# board.net
KiCad netlist of a schematic drawn in EAGLE
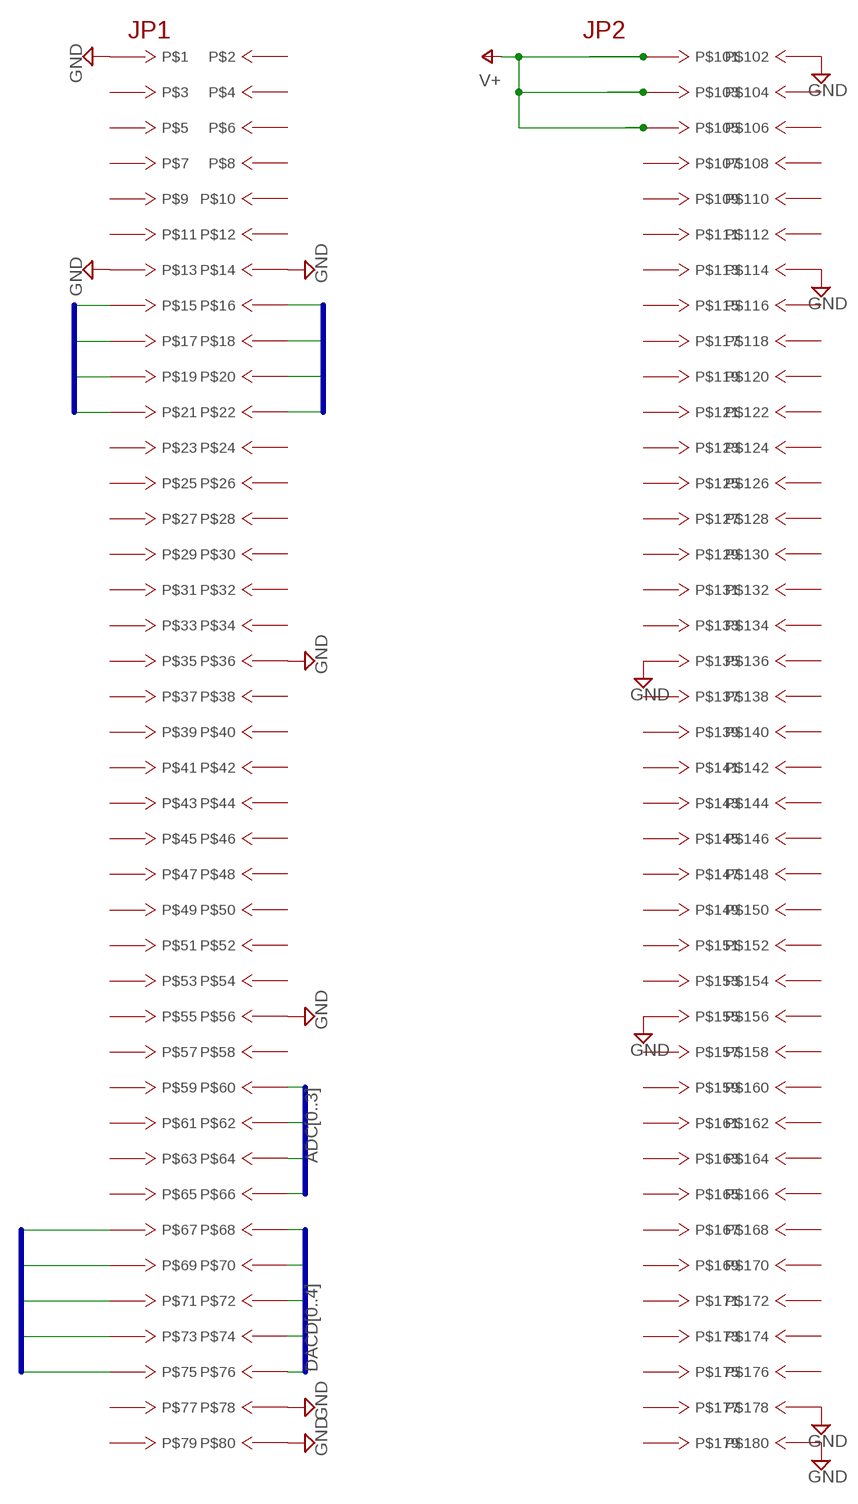
[diagram p0: schematic, sheet 1]
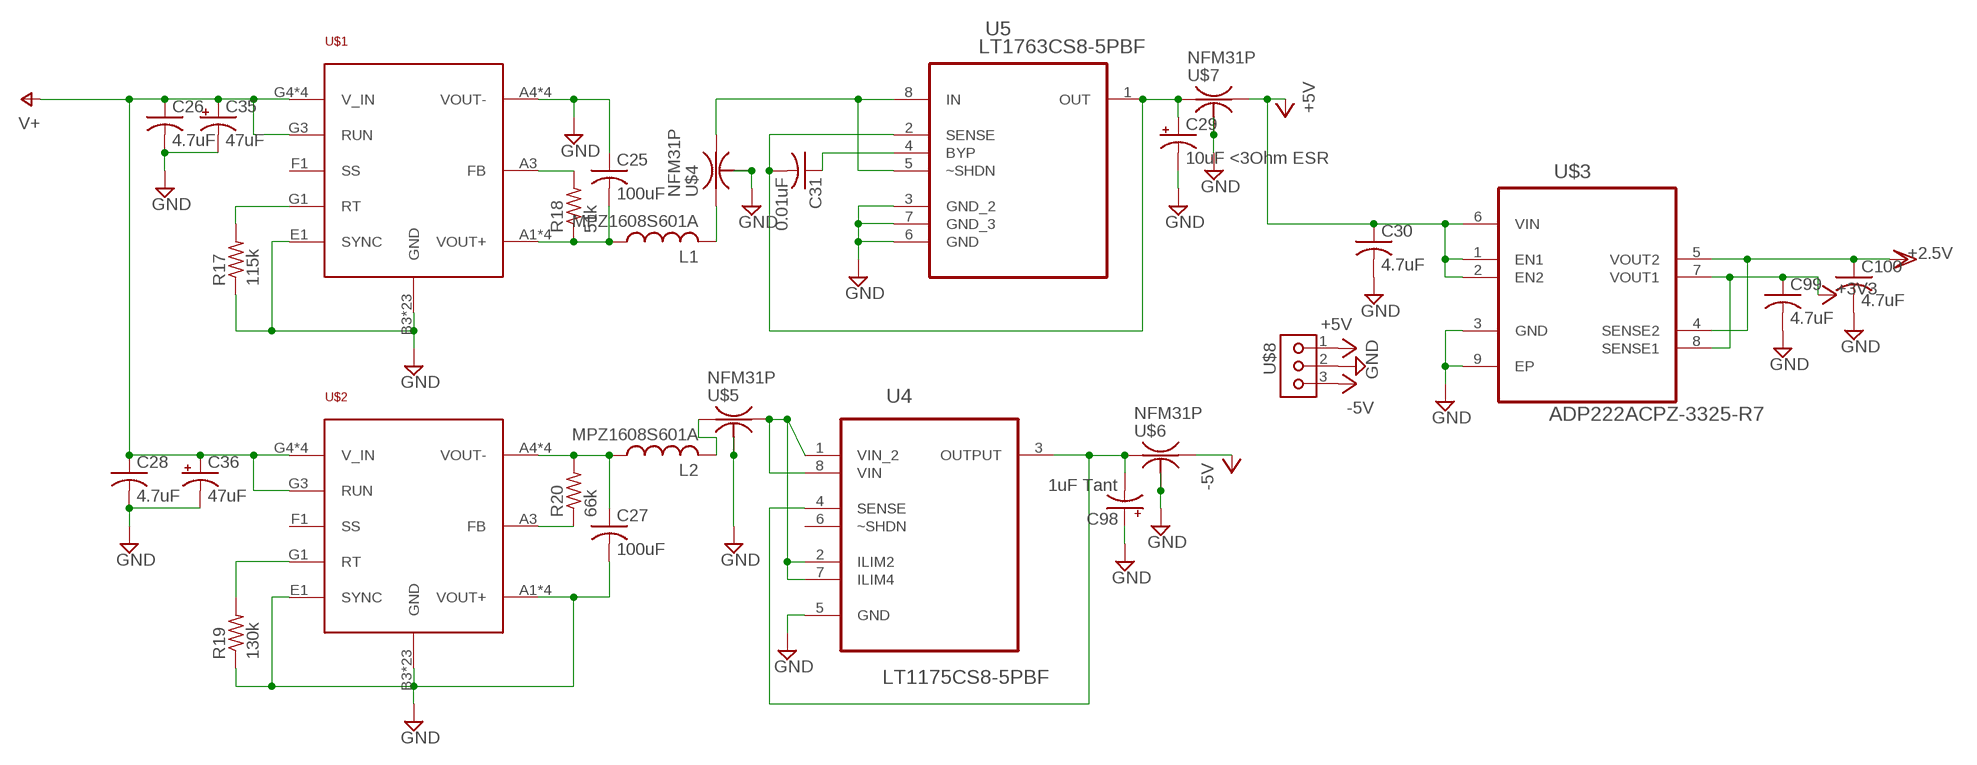
[diagram p1: schematic, sheet 2]
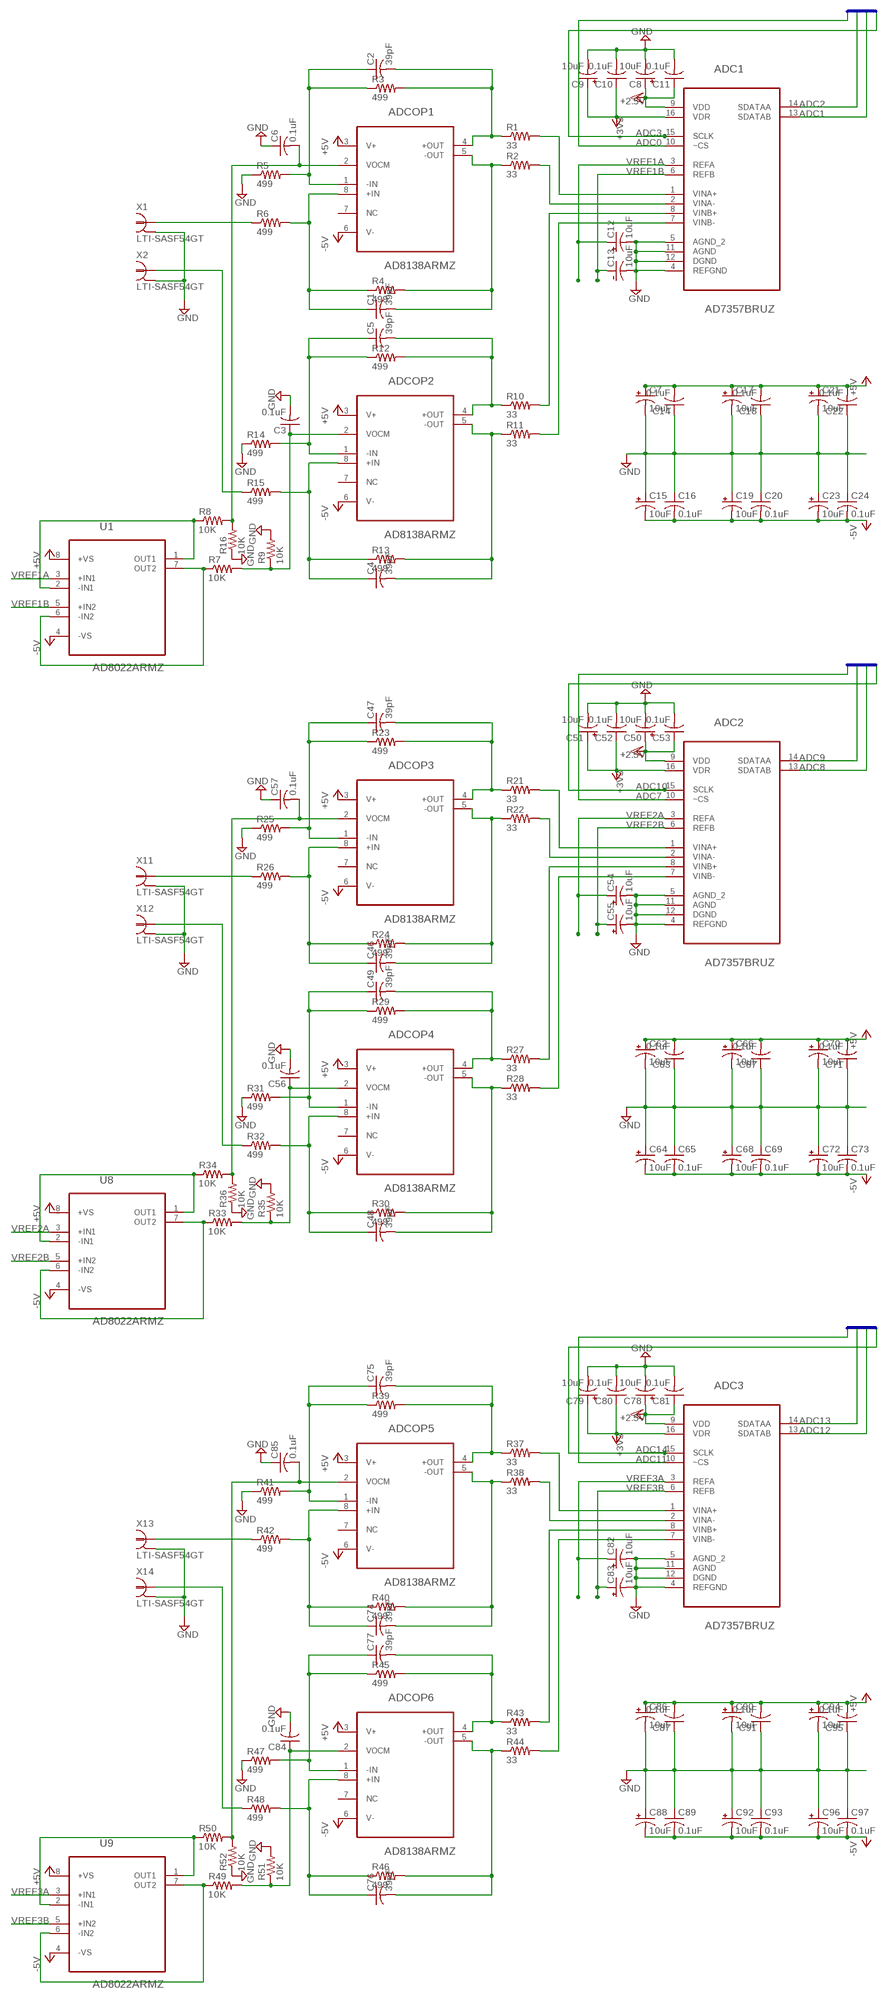
[diagram p2: schematic, sheet 3]
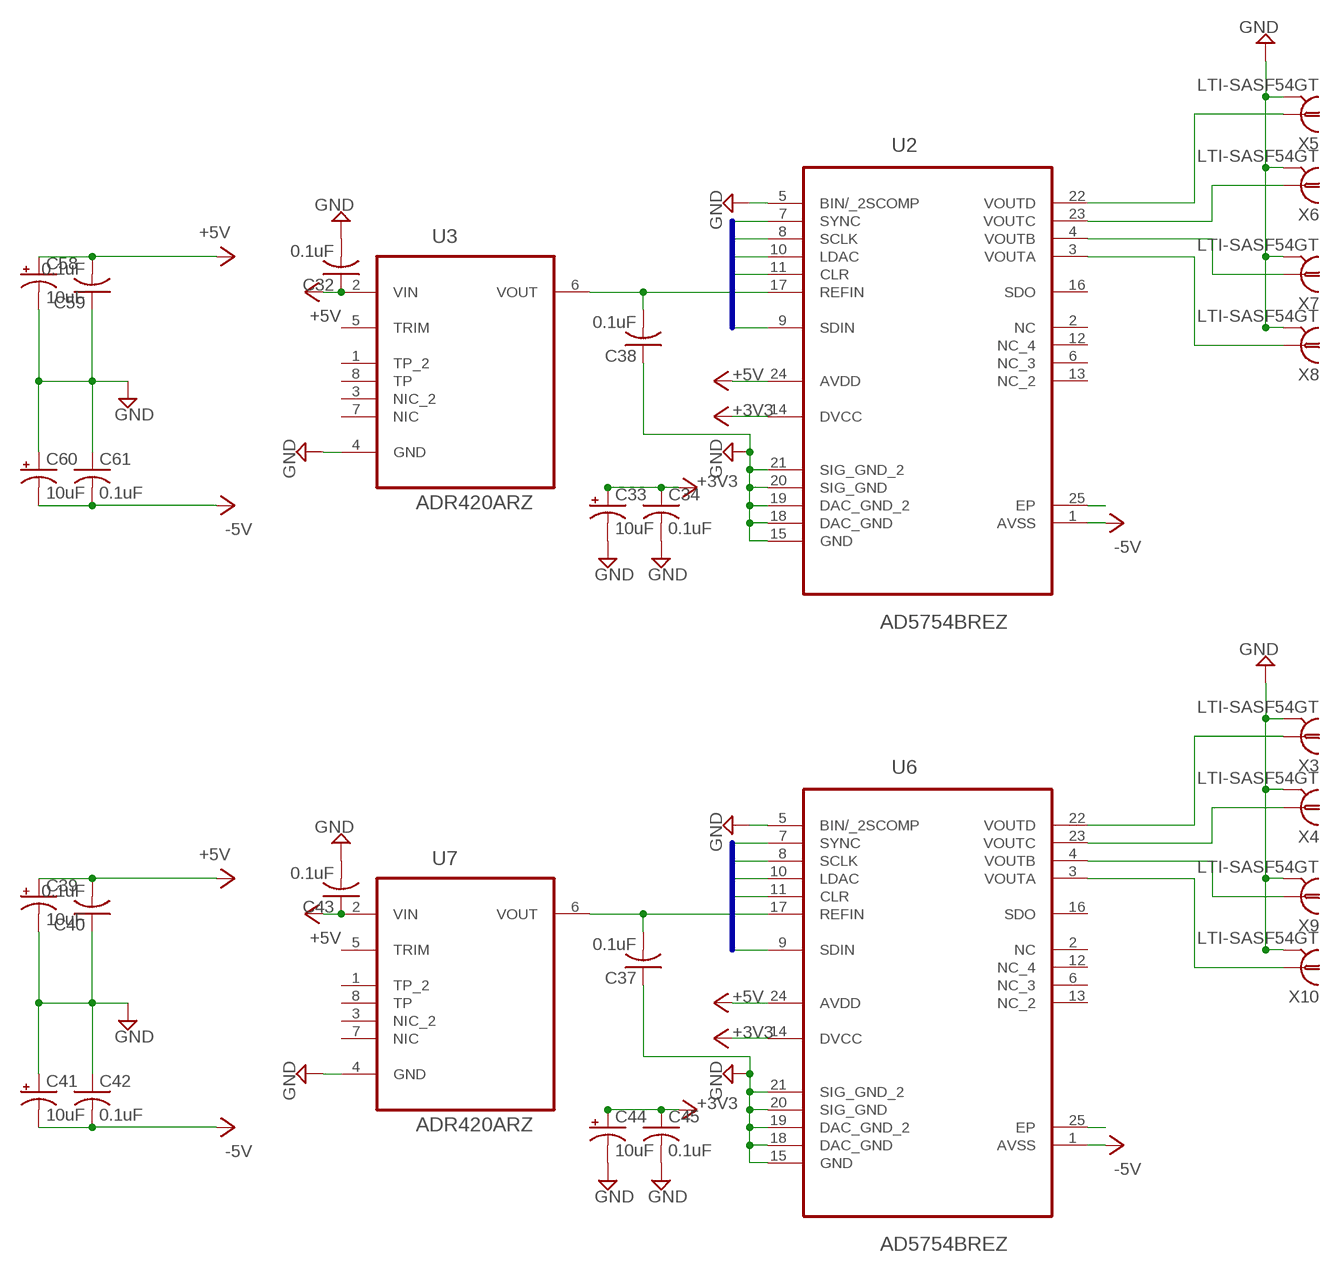
[diagram p3: schematic, sheet 4]

(export (version "E")
  (design (tool "Eeschema 10.0.6"))
  (components
    (comp (ref "J1")
      (value "XEM6310")
      (footprint "eagle-import:XEM6310")
      (libsource (lib "eagle-import") (part "XEM6310"))
    )
    (comp (ref "C32")
      (value "0.1uF")
      (footprint "eagle-import:C0603")
      (libsource (lib "eagle-import") (part "C-USC0603"))
    )
    (comp (ref "C33")
      (value "10uF")
      (footprint "eagle-import:C0603T")
      (libsource (lib "eagle-import") (part "CPOL-US"))
    )
    (comp (ref "C34")
      (value "0.1uF")
      (footprint "eagle-import:C0603")
      (libsource (lib "eagle-import") (part "C-USC0603"))
    )
    (comp (ref "C37")
      (value "0.1uF")
      (footprint "eagle-import:C0603")
      (libsource (lib "eagle-import") (part "C-USC0603"))
    )
    (comp (ref "C38")
      (value "0.1uF")
      (footprint "eagle-import:C0603")
      (libsource (lib "eagle-import") (part "C-USC0603"))
    )
    (comp (ref "C39")
      (value "10uF")
      (footprint "eagle-import:C0603T")
      (libsource (lib "eagle-import") (part "CPOL-US"))
    )
    (comp (ref "C40")
      (value "0.1uF")
      (footprint "eagle-import:C0603")
      (libsource (lib "eagle-import") (part "C-USC0603"))
    )
    (comp (ref "C41")
      (value "10uF")
      (footprint "eagle-import:C0603T")
      (libsource (lib "eagle-import") (part "CPOL-US"))
    )
    (comp (ref "C42")
      (value "0.1uF")
      (footprint "eagle-import:C0603")
      (libsource (lib "eagle-import") (part "C-USC0603"))
    )
    (comp (ref "C43")
      (value "0.1uF")
      (footprint "eagle-import:C0603")
      (libsource (lib "eagle-import") (part "C-USC0603"))
    )
    (comp (ref "C44")
      (value "10uF")
      (footprint "eagle-import:C0603T")
      (libsource (lib "eagle-import") (part "CPOL-US"))
    )
    (comp (ref "C45")
      (value "0.1uF")
      (footprint "eagle-import:C0603")
      (libsource (lib "eagle-import") (part "C-USC0603"))
    )
    (comp (ref "C58")
      (value "10uF")
      (footprint "eagle-import:C0603T")
      (libsource (lib "eagle-import") (part "CPOL-US"))
    )
    (comp (ref "C59")
      (value "0.1uF")
      (footprint "eagle-import:C0603")
      (libsource (lib "eagle-import") (part "C-USC0603"))
    )
    (comp (ref "C60")
      (value "10uF")
      (footprint "eagle-import:C0603T")
      (libsource (lib "eagle-import") (part "CPOL-US"))
    )
    (comp (ref "C61")
      (value "0.1uF")
      (footprint "eagle-import:C0603")
      (libsource (lib "eagle-import") (part "C-USC0603"))
    )
    (comp (ref "U2")
      (value "AD5754BREZ")
      (footprint "eagle-import:SOP65P640X120-25N")
      (libsource (lib "eagle-import") (part "AD5754BREZ"))
    )
    (comp (ref "U3")
      (value "ADR420ARZ")
      (footprint "eagle-import:SOIC127P600X175-8N")
      (libsource (lib "eagle-import") (part "ADR420ARZ"))
    )
    (comp (ref "U6")
      (value "AD5754BREZ")
      (footprint "eagle-import:SOP65P640X120-25N")
      (libsource (lib "eagle-import") (part "AD5754BREZ"))
    )
    (comp (ref "U7")
      (value "ADR420ARZ")
      (footprint "eagle-import:SOIC127P600X175-8N")
      (libsource (lib "eagle-import") (part "ADR420ARZ"))
    )
    (comp (ref "X3")
      (value "LTI-SASF54GT")
      (footprint "eagle-import:LTI-SASF54GT")
      (libsource (lib "eagle-import") (part "LTI-SASF54GT"))
    )
    (comp (ref "X4")
      (value "LTI-SASF54GT")
      (footprint "eagle-import:LTI-SASF54GT")
      (libsource (lib "eagle-import") (part "LTI-SASF54GT"))
    )
    (comp (ref "X5")
      (value "LTI-SASF54GT")
      (footprint "eagle-import:LTI-SASF54GT")
      (libsource (lib "eagle-import") (part "LTI-SASF54GT"))
    )
    (comp (ref "X6")
      (value "LTI-SASF54GT")
      (footprint "eagle-import:LTI-SASF54GT")
      (libsource (lib "eagle-import") (part "LTI-SASF54GT"))
    )
    (comp (ref "X7")
      (value "LTI-SASF54GT")
      (footprint "eagle-import:LTI-SASF54GT")
      (libsource (lib "eagle-import") (part "LTI-SASF54GT"))
    )
    (comp (ref "X8")
      (value "LTI-SASF54GT")
      (footprint "eagle-import:LTI-SASF54GT")
      (libsource (lib "eagle-import") (part "LTI-SASF54GT"))
    )
    (comp (ref "X9")
      (value "LTI-SASF54GT")
      (footprint "eagle-import:LTI-SASF54GT")
      (libsource (lib "eagle-import") (part "LTI-SASF54GT"))
    )
    (comp (ref "X10")
      (value "LTI-SASF54GT")
      (footprint "eagle-import:LTI-SASF54GT")
      (libsource (lib "eagle-import") (part "LTI-SASF54GT"))
    )
    (comp (ref "C25")
      (value "100uF")
      (footprint "eagle-import:C1210")
      (libsource (lib "eagle-import") (part "C-USC1210"))
    )
    (comp (ref "C26")
      (value "4.7uF")
      (footprint "eagle-import:C0603")
      (libsource (lib "eagle-import") (part "C-USC0603"))
    )
    (comp (ref "C27")
      (value "100uF")
      (footprint "eagle-import:C1210")
      (libsource (lib "eagle-import") (part "C-USC1210"))
    )
    (comp (ref "C28")
      (value "4.7uF")
      (footprint "eagle-import:C0603")
      (libsource (lib "eagle-import") (part "C-USC0603"))
    )
    (comp (ref "C29")
      (value "10uF <3Ohm ESR")
      (footprint "eagle-import:C0603T")
      (libsource (lib "eagle-import") (part "CPOL-US"))
    )
    (comp (ref "C30")
      (value "4.7uF")
      (footprint "eagle-import:C0603")
      (libsource (lib "eagle-import") (part "C-USC0603"))
    )
    (comp (ref "C31")
      (value "0.01uF")
      (footprint "eagle-import:C0603")
      (libsource (lib "eagle-import") (part "C-USC0603"))
    )
    (comp (ref "C35")
      (value "47uF")
      (footprint "eagle-import:UD-4X5,8_NICHICON")
      (libsource (lib "eagle-import") (part "CPOL-USUD-4X5,8"))
    )
    (comp (ref "C36")
      (value "47uF")
      (footprint "eagle-import:UD-4X5,8_NICHICON")
      (libsource (lib "eagle-import") (part "CPOL-USUD-4X5,8"))
    )
    (comp (ref "C98")
      (value "1uF Tant")
      (footprint "eagle-import:C0603T")
      (libsource (lib "eagle-import") (part "CPOL-US"))
    )
    (comp (ref "C99")
      (value "4.7uF")
      (footprint "eagle-import:C0603")
      (libsource (lib "eagle-import") (part "C-USC0603"))
    )
    (comp (ref "C100")
      (value "4.7uF")
      (footprint "eagle-import:C0603")
      (libsource (lib "eagle-import") (part "C-USC0603"))
    )
    (comp (ref "L1")
      (value "MPZ1608S601A")
      (footprint "eagle-import:C0603")
      (libsource (lib "eagle-import") (part "L-US"))
    )
    (comp (ref "L2")
      (value "MPZ1608S601A")
      (footprint "eagle-import:C0603")
      (libsource (lib "eagle-import") (part "L-US"))
    )
    (comp (ref "R17")
      (value "115k")
      (footprint "eagle-import:R0603")
      (libsource (lib "eagle-import") (part "R-US_R0603"))
    )
    (comp (ref "R18")
      (value "51k")
      (footprint "eagle-import:R0603")
      (libsource (lib "eagle-import") (part "R-US_R0603"))
    )
    (comp (ref "R19")
      (value "130k")
      (footprint "eagle-import:R0603")
      (libsource (lib "eagle-import") (part "R-US_R0603"))
    )
    (comp (ref "R20")
      (value "66k")
      (footprint "eagle-import:R0603")
      (libsource (lib "eagle-import") (part "R-US_R0603"))
    )
    (comp (ref "U$1")
      (value "LTM8045")
      (footprint "eagle-import:BGA-40")
      (libsource (lib "eagle-import") (part "LTM8045"))
    )
    (comp (ref "U$2")
      (value "LTM8045")
      (footprint "eagle-import:BGA-40")
      (libsource (lib "eagle-import") (part "LTM8045"))
    )
    (comp (ref "U$3")
      (value "ADP222ACPZ-3325-R7")
      (footprint "eagle-import:QFN50P200X200X60-9N")
      (libsource (lib "eagle-import") (part "ADP222ACPZ-3325-R7"))
    )
    (comp (ref "U$4")
      (value "NFM31P")
      (footprint "eagle-import:NFM31P")
      (libsource (lib "eagle-import") (part "NFM31P"))
    )
    (comp (ref "U$5")
      (value "NFM31P")
      (footprint "eagle-import:NFM31P")
      (libsource (lib "eagle-import") (part "NFM31P"))
    )
    (comp (ref "U$6")
      (value "NFM31P")
      (footprint "eagle-import:NFM31P")
      (libsource (lib "eagle-import") (part "NFM31P"))
    )
    (comp (ref "U$7")
      (value "NFM31P")
      (footprint "eagle-import:NFM31P")
      (libsource (lib "eagle-import") (part "NFM31P"))
    )
    (comp (ref "U$8")
      (value "KK3V")
      (footprint "eagle-import:KK-V-3")
      (libsource (lib "eagle-import") (part "KK3V"))
    )
    (comp (ref "U4")
      (value "LT1175CS8-5PBF")
      (footprint "eagle-import:SOIC127P600X175-8N")
      (fields (field (name "MPN") "LT1175CS8-5#PBF"))
      (libsource (lib "eagle-import") (part "LT1175CS8-5PBF"))
    )
    (comp (ref "U5")
      (value "LT1763CS8-5PBF")
      (footprint "eagle-import:SOIC127P600X175-8N")
      (fields (field (name "MPN") "LT1763CS8-5#PBF"))
      (libsource (lib "eagle-import") (part "LT1763CS8-5PBF"))
    )
    (comp (ref "ADC1")
      (value "AD7357BRUZ")
      (footprint "eagle-import:SOP65P640X120-16N")
      (libsource (lib "eagle-import") (part "AD7357BRUZ"))
    )
    (comp (ref "ADC2")
      (value "AD7357BRUZ")
      (footprint "eagle-import:SOP65P640X120-16N")
      (libsource (lib "eagle-import") (part "AD7357BRUZ"))
    )
    (comp (ref "ADC3")
      (value "AD7357BRUZ")
      (footprint "eagle-import:SOP65P640X120-16N")
      (libsource (lib "eagle-import") (part "AD7357BRUZ"))
    )
    (comp (ref "ADCOP1")
      (value "AD8138ARMZ")
      (footprint "eagle-import:SOP65P490X110-8N")
      (libsource (lib "eagle-import") (part "AD8138ARMZ"))
    )
    (comp (ref "ADCOP2")
      (value "AD8138ARMZ")
      (footprint "eagle-import:SOP65P490X110-8N")
      (libsource (lib "eagle-import") (part "AD8138ARMZ"))
    )
    (comp (ref "ADCOP3")
      (value "AD8138ARMZ")
      (footprint "eagle-import:SOP65P490X110-8N")
      (libsource (lib "eagle-import") (part "AD8138ARMZ"))
    )
    (comp (ref "ADCOP4")
      (value "AD8138ARMZ")
      (footprint "eagle-import:SOP65P490X110-8N")
      (libsource (lib "eagle-import") (part "AD8138ARMZ"))
    )
    (comp (ref "ADCOP5")
      (value "AD8138ARMZ")
      (footprint "eagle-import:SOP65P490X110-8N")
      (libsource (lib "eagle-import") (part "AD8138ARMZ"))
    )
    (comp (ref "ADCOP6")
      (value "AD8138ARMZ")
      (footprint "eagle-import:SOP65P490X110-8N")
      (libsource (lib "eagle-import") (part "AD8138ARMZ"))
    )
    (comp (ref "C1")
      (value "39pF")
      (footprint "eagle-import:C0603")
      (libsource (lib "eagle-import") (part "C-USC0603"))
    )
    (comp (ref "C2")
      (value "39pF")
      (footprint "eagle-import:C0603")
      (libsource (lib "eagle-import") (part "C-USC0603"))
    )
    (comp (ref "C3")
      (value "0.1uF")
      (footprint "eagle-import:C0603")
      (libsource (lib "eagle-import") (part "C-USC0603"))
    )
    (comp (ref "C4")
      (value "39pF")
      (footprint "eagle-import:C0603")
      (libsource (lib "eagle-import") (part "C-USC0603"))
    )
    (comp (ref "C5")
      (value "39pF")
      (footprint "eagle-import:C0603")
      (libsource (lib "eagle-import") (part "C-USC0603"))
    )
    (comp (ref "C6")
      (value "0.1uF")
      (footprint "eagle-import:C0603")
      (libsource (lib "eagle-import") (part "C-USC0603"))
    )
    (comp (ref "C7")
      (value "10uF")
      (footprint "eagle-import:C0603T")
      (libsource (lib "eagle-import") (part "CPOL-US"))
    )
    (comp (ref "C8")
      (value "10uF")
      (footprint "eagle-import:C0603T")
      (libsource (lib "eagle-import") (part "CPOL-US"))
    )
    (comp (ref "C9")
      (value "10uF")
      (footprint "eagle-import:C0603T")
      (libsource (lib "eagle-import") (part "CPOL-US"))
    )
    (comp (ref "C10")
      (value "0.1uF")
      (footprint "eagle-import:C0603")
      (libsource (lib "eagle-import") (part "C-USC0603"))
    )
    (comp (ref "C11")
      (value "0.1uF")
      (footprint "eagle-import:C0603")
      (libsource (lib "eagle-import") (part "C-USC0603"))
    )
    (comp (ref "C12")
      (value "10uF")
      (footprint "eagle-import:C0603T")
      (libsource (lib "eagle-import") (part "CPOL-US"))
    )
    (comp (ref "C13")
      (value "10uF")
      (footprint "eagle-import:C0603T")
      (libsource (lib "eagle-import") (part "CPOL-US"))
    )
    (comp (ref "C14")
      (value "0.1uF")
      (footprint "eagle-import:C0603")
      (libsource (lib "eagle-import") (part "C-USC0603"))
    )
    (comp (ref "C15")
      (value "10uF")
      (footprint "eagle-import:C0603T")
      (libsource (lib "eagle-import") (part "CPOL-US"))
    )
    (comp (ref "C16")
      (value "0.1uF")
      (footprint "eagle-import:C0603")
      (libsource (lib "eagle-import") (part "C-USC0603"))
    )
    (comp (ref "C17")
      (value "10uF")
      (footprint "eagle-import:C0603T")
      (libsource (lib "eagle-import") (part "CPOL-US"))
    )
    (comp (ref "C18")
      (value "0.1uF")
      (footprint "eagle-import:C0603")
      (libsource (lib "eagle-import") (part "C-USC0603"))
    )
    (comp (ref "C19")
      (value "10uF")
      (footprint "eagle-import:C0603T")
      (libsource (lib "eagle-import") (part "CPOL-US"))
    )
    (comp (ref "C20")
      (value "0.1uF")
      (footprint "eagle-import:C0603")
      (libsource (lib "eagle-import") (part "C-USC0603"))
    )
    (comp (ref "C21")
      (value "10uF")
      (footprint "eagle-import:C0603T")
      (libsource (lib "eagle-import") (part "CPOL-US"))
    )
    (comp (ref "C22")
      (value "0.1uF")
      (footprint "eagle-import:C0603")
      (libsource (lib "eagle-import") (part "C-USC0603"))
    )
    (comp (ref "C23")
      (value "10uF")
      (footprint "eagle-import:C0603T")
      (libsource (lib "eagle-import") (part "CPOL-US"))
    )
    (comp (ref "C24")
      (value "0.1uF")
      (footprint "eagle-import:C0603")
      (libsource (lib "eagle-import") (part "C-USC0603"))
    )
    (comp (ref "C46")
      (value "39pF")
      (footprint "eagle-import:C0603")
      (libsource (lib "eagle-import") (part "C-USC0603"))
    )
    (comp (ref "C47")
      (value "39pF")
      (footprint "eagle-import:C0603")
      (libsource (lib "eagle-import") (part "C-USC0603"))
    )
    (comp (ref "C48")
      (value "39pF")
      (footprint "eagle-import:C0603")
      (libsource (lib "eagle-import") (part "C-USC0603"))
    )
    (comp (ref "C49")
      (value "39pF")
      (footprint "eagle-import:C0603")
      (libsource (lib "eagle-import") (part "C-USC0603"))
    )
    (comp (ref "C50")
      (value "10uF")
      (footprint "eagle-import:C0603T")
      (libsource (lib "eagle-import") (part "CPOL-US"))
    )
    (comp (ref "C51")
      (value "10uF")
      (footprint "eagle-import:C0603T")
      (libsource (lib "eagle-import") (part "CPOL-US"))
    )
    (comp (ref "C52")
      (value "0.1uF")
      (footprint "eagle-import:C0603")
      (libsource (lib "eagle-import") (part "C-USC0603"))
    )
    (comp (ref "C53")
      (value "0.1uF")
      (footprint "eagle-import:C0603")
      (libsource (lib "eagle-import") (part "C-USC0603"))
    )
    (comp (ref "C54")
      (value "10uF")
      (footprint "eagle-import:C0603T")
      (libsource (lib "eagle-import") (part "CPOL-US"))
    )
    (comp (ref "C55")
      (value "10uF")
      (footprint "eagle-import:C0603T")
      (libsource (lib "eagle-import") (part "CPOL-US"))
    )
    (comp (ref "C56")
      (value "0.1uF")
      (footprint "eagle-import:C0603")
      (libsource (lib "eagle-import") (part "C-USC0603"))
    )
    (comp (ref "C57")
      (value "0.1uF")
      (footprint "eagle-import:C0603")
      (libsource (lib "eagle-import") (part "C-USC0603"))
    )
    (comp (ref "C62")
      (value "10uF")
      (footprint "eagle-import:C0603T")
      (libsource (lib "eagle-import") (part "CPOL-US"))
    )
    (comp (ref "C63")
      (value "0.1uF")
      (footprint "eagle-import:C0603")
      (libsource (lib "eagle-import") (part "C-USC0603"))
    )
    (comp (ref "C64")
      (value "10uF")
      (footprint "eagle-import:C0603T")
      (libsource (lib "eagle-import") (part "CPOL-US"))
    )
    (comp (ref "C65")
      (value "0.1uF")
      (footprint "eagle-import:C0603")
      (libsource (lib "eagle-import") (part "C-USC0603"))
    )
    (comp (ref "C66")
      (value "10uF")
      (footprint "eagle-import:C0603T")
      (libsource (lib "eagle-import") (part "CPOL-US"))
    )
    (comp (ref "C67")
      (value "0.1uF")
      (footprint "eagle-import:C0603")
      (libsource (lib "eagle-import") (part "C-USC0603"))
    )
    (comp (ref "C68")
      (value "10uF")
      (footprint "eagle-import:C0603T")
      (libsource (lib "eagle-import") (part "CPOL-US"))
    )
    (comp (ref "C69")
      (value "0.1uF")
      (footprint "eagle-import:C0603")
      (libsource (lib "eagle-import") (part "C-USC0603"))
    )
    (comp (ref "C70")
      (value "10uF")
      (footprint "eagle-import:C0603T")
      (libsource (lib "eagle-import") (part "CPOL-US"))
    )
    (comp (ref "C71")
      (value "0.1uF")
      (footprint "eagle-import:C0603")
      (libsource (lib "eagle-import") (part "C-USC0603"))
    )
    (comp (ref "C72")
      (value "10uF")
      (footprint "eagle-import:C0603T")
      (libsource (lib "eagle-import") (part "CPOL-US"))
    )
    (comp (ref "C73")
      (value "0.1uF")
      (footprint "eagle-import:C0603")
      (libsource (lib "eagle-import") (part "C-USC0603"))
    )
    (comp (ref "C74")
      (value "39pF")
      (footprint "eagle-import:C0603")
      (libsource (lib "eagle-import") (part "C-USC0603"))
    )
    (comp (ref "C75")
      (value "39pF")
      (footprint "eagle-import:C0603")
      (libsource (lib "eagle-import") (part "C-USC0603"))
    )
    (comp (ref "C76")
      (value "39pF")
      (footprint "eagle-import:C0603")
      (libsource (lib "eagle-import") (part "C-USC0603"))
    )
    (comp (ref "C77")
      (value "39pF")
      (footprint "eagle-import:C0603")
      (libsource (lib "eagle-import") (part "C-USC0603"))
    )
    (comp (ref "C78")
      (value "10uF")
      (footprint "eagle-import:C0603T")
      (libsource (lib "eagle-import") (part "CPOL-US"))
    )
    (comp (ref "C79")
      (value "10uF")
      (footprint "eagle-import:C0603T")
      (libsource (lib "eagle-import") (part "CPOL-US"))
    )
    (comp (ref "C80")
      (value "0.1uF")
      (footprint "eagle-import:C0603")
      (libsource (lib "eagle-import") (part "C-USC0603"))
    )
    (comp (ref "C81")
      (value "0.1uF")
      (footprint "eagle-import:C0603")
      (libsource (lib "eagle-import") (part "C-USC0603"))
    )
    (comp (ref "C82")
      (value "10uF")
      (footprint "eagle-import:C0603T")
      (libsource (lib "eagle-import") (part "CPOL-US"))
    )
    (comp (ref "C83")
      (value "10uF")
      (footprint "eagle-import:C0603T")
      (libsource (lib "eagle-import") (part "CPOL-US"))
    )
    (comp (ref "C84")
      (value "0.1uF")
      (footprint "eagle-import:C0603")
      (libsource (lib "eagle-import") (part "C-USC0603"))
    )
    (comp (ref "C85")
      (value "0.1uF")
      (footprint "eagle-import:C0603")
      (libsource (lib "eagle-import") (part "C-USC0603"))
    )
    (comp (ref "C86")
      (value "10uF")
      (footprint "eagle-import:C0603T")
      (libsource (lib "eagle-import") (part "CPOL-US"))
    )
    (comp (ref "C87")
      (value "0.1uF")
      (footprint "eagle-import:C0603")
      (libsource (lib "eagle-import") (part "C-USC0603"))
    )
    (comp (ref "C88")
      (value "10uF")
      (footprint "eagle-import:C0603T")
      (libsource (lib "eagle-import") (part "CPOL-US"))
    )
    (comp (ref "C89")
      (value "0.1uF")
      (footprint "eagle-import:C0603")
      (libsource (lib "eagle-import") (part "C-USC0603"))
    )
    (comp (ref "C90")
      (value "10uF")
      (footprint "eagle-import:C0603T")
      (libsource (lib "eagle-import") (part "CPOL-US"))
    )
    (comp (ref "C91")
      (value "0.1uF")
      (footprint "eagle-import:C0603")
      (libsource (lib "eagle-import") (part "C-USC0603"))
    )
    (comp (ref "C92")
      (value "10uF")
      (footprint "eagle-import:C0603T")
      (libsource (lib "eagle-import") (part "CPOL-US"))
    )
    (comp (ref "C93")
      (value "0.1uF")
      (footprint "eagle-import:C0603")
      (libsource (lib "eagle-import") (part "C-USC0603"))
    )
    (comp (ref "C94")
      (value "10uF")
      (footprint "eagle-import:C0603T")
      (libsource (lib "eagle-import") (part "CPOL-US"))
    )
    (comp (ref "C95")
      (value "0.1uF")
      (footprint "eagle-import:C0603")
      (libsource (lib "eagle-import") (part "C-USC0603"))
    )
    (comp (ref "C96")
      (value "10uF")
      (footprint "eagle-import:C0603T")
      (libsource (lib "eagle-import") (part "CPOL-US"))
    )
    (comp (ref "C97")
      (value "0.1uF")
      (footprint "eagle-import:C0603")
      (libsource (lib "eagle-import") (part "C-USC0603"))
    )
    (comp (ref "R1")
      (value "33")
      (footprint "eagle-import:R0603")
      (libsource (lib "eagle-import") (part "R-US_R0603"))
    )
    (comp (ref "R2")
      (value "33")
      (footprint "eagle-import:R0603")
      (libsource (lib "eagle-import") (part "R-US_R0603"))
    )
    (comp (ref "R3")
      (value "499")
      (footprint "eagle-import:R0603")
      (libsource (lib "eagle-import") (part "R-US_R0603"))
    )
    (comp (ref "R4")
      (value "499")
      (footprint "eagle-import:R0603")
      (libsource (lib "eagle-import") (part "R-US_R0603"))
    )
    (comp (ref "R5")
      (value "499")
      (footprint "eagle-import:R0603")
      (libsource (lib "eagle-import") (part "R-US_R0603"))
    )
    (comp (ref "R6")
      (value "499")
      (footprint "eagle-import:R0603")
      (libsource (lib "eagle-import") (part "R-US_R0603"))
    )
    (comp (ref "R7")
      (value "10K")
      (footprint "eagle-import:R0603")
      (libsource (lib "eagle-import") (part "R-US_R0603"))
    )
    (comp (ref "R8")
      (value "10K")
      (footprint "eagle-import:R0603")
      (libsource (lib "eagle-import") (part "R-US_R0603"))
    )
    (comp (ref "R9")
      (value "10K")
      (footprint "eagle-import:R0603")
      (libsource (lib "eagle-import") (part "R-US_R0603"))
    )
    (comp (ref "R10")
      (value "33")
      (footprint "eagle-import:R0603")
      (libsource (lib "eagle-import") (part "R-US_R0603"))
    )
    (comp (ref "R11")
      (value "33")
      (footprint "eagle-import:R0603")
      (libsource (lib "eagle-import") (part "R-US_R0603"))
    )
    (comp (ref "R12")
      (value "499")
      (footprint "eagle-import:R0603")
      (libsource (lib "eagle-import") (part "R-US_R0603"))
    )
    (comp (ref "R13")
      (value "499")
      (footprint "eagle-import:R0603")
      (libsource (lib "eagle-import") (part "R-US_R0603"))
    )
    (comp (ref "R14")
      (value "499")
      (footprint "eagle-import:R0603")
      (libsource (lib "eagle-import") (part "R-US_R0603"))
    )
    (comp (ref "R15")
      (value "499")
      (footprint "eagle-import:R0603")
      (libsource (lib "eagle-import") (part "R-US_R0603"))
    )
    (comp (ref "R16")
      (value "10K")
      (footprint "eagle-import:R0603")
      (libsource (lib "eagle-import") (part "R-US_R0603"))
    )
    (comp (ref "R21")
      (value "33")
      (footprint "eagle-import:R0603")
      (libsource (lib "eagle-import") (part "R-US_R0603"))
    )
    (comp (ref "R22")
      (value "33")
      (footprint "eagle-import:R0603")
      (libsource (lib "eagle-import") (part "R-US_R0603"))
    )
    (comp (ref "R23")
      (value "499")
      (footprint "eagle-import:R0603")
      (libsource (lib "eagle-import") (part "R-US_R0603"))
    )
    (comp (ref "R24")
      (value "499")
      (footprint "eagle-import:R0603")
      (libsource (lib "eagle-import") (part "R-US_R0603"))
    )
    (comp (ref "R25")
      (value "499")
      (footprint "eagle-import:R0603")
      (libsource (lib "eagle-import") (part "R-US_R0603"))
    )
    (comp (ref "R26")
      (value "499")
      (footprint "eagle-import:R0603")
      (libsource (lib "eagle-import") (part "R-US_R0603"))
    )
    (comp (ref "R27")
      (value "33")
      (footprint "eagle-import:R0603")
      (libsource (lib "eagle-import") (part "R-US_R0603"))
    )
    (comp (ref "R28")
      (value "33")
      (footprint "eagle-import:R0603")
      (libsource (lib "eagle-import") (part "R-US_R0603"))
    )
    (comp (ref "R29")
      (value "499")
      (footprint "eagle-import:R0603")
      (libsource (lib "eagle-import") (part "R-US_R0603"))
    )
    (comp (ref "R30")
      (value "499")
      (footprint "eagle-import:R0603")
      (libsource (lib "eagle-import") (part "R-US_R0603"))
    )
    (comp (ref "R31")
      (value "499")
      (footprint "eagle-import:R0603")
      (libsource (lib "eagle-import") (part "R-US_R0603"))
    )
    (comp (ref "R32")
      (value "499")
      (footprint "eagle-import:R0603")
      (libsource (lib "eagle-import") (part "R-US_R0603"))
    )
    (comp (ref "R33")
      (value "10K")
      (footprint "eagle-import:R0603")
      (libsource (lib "eagle-import") (part "R-US_R0603"))
    )
    (comp (ref "R34")
      (value "10K")
      (footprint "eagle-import:R0603")
      (libsource (lib "eagle-import") (part "R-US_R0603"))
    )
    (comp (ref "R35")
      (value "10K")
      (footprint "eagle-import:R0603")
      (libsource (lib "eagle-import") (part "R-US_R0603"))
    )
    (comp (ref "R36")
      (value "10K")
      (footprint "eagle-import:R0603")
      (libsource (lib "eagle-import") (part "R-US_R0603"))
    )
    (comp (ref "R37")
      (value "33")
      (footprint "eagle-import:R0603")
      (libsource (lib "eagle-import") (part "R-US_R0603"))
    )
    (comp (ref "R38")
      (value "33")
      (footprint "eagle-import:R0603")
      (libsource (lib "eagle-import") (part "R-US_R0603"))
    )
    (comp (ref "R39")
      (value "499")
      (footprint "eagle-import:R0603")
      (libsource (lib "eagle-import") (part "R-US_R0603"))
    )
    (comp (ref "R40")
      (value "499")
      (footprint "eagle-import:R0603")
      (libsource (lib "eagle-import") (part "R-US_R0603"))
    )
    (comp (ref "R41")
      (value "499")
      (footprint "eagle-import:R0603")
      (libsource (lib "eagle-import") (part "R-US_R0603"))
    )
    (comp (ref "R42")
      (value "499")
      (footprint "eagle-import:R0603")
      (libsource (lib "eagle-import") (part "R-US_R0603"))
    )
    (comp (ref "R43")
      (value "33")
      (footprint "eagle-import:R0603")
      (libsource (lib "eagle-import") (part "R-US_R0603"))
    )
    (comp (ref "R44")
      (value "33")
      (footprint "eagle-import:R0603")
      (libsource (lib "eagle-import") (part "R-US_R0603"))
    )
    (comp (ref "R45")
      (value "499")
      (footprint "eagle-import:R0603")
      (libsource (lib "eagle-import") (part "R-US_R0603"))
    )
    (comp (ref "R46")
      (value "499")
      (footprint "eagle-import:R0603")
      (libsource (lib "eagle-import") (part "R-US_R0603"))
    )
    (comp (ref "R47")
      (value "499")
      (footprint "eagle-import:R0603")
      (libsource (lib "eagle-import") (part "R-US_R0603"))
    )
    (comp (ref "R48")
      (value "499")
      (footprint "eagle-import:R0603")
      (libsource (lib "eagle-import") (part "R-US_R0603"))
    )
    (comp (ref "R49")
      (value "10K")
      (footprint "eagle-import:R0603")
      (libsource (lib "eagle-import") (part "R-US_R0603"))
    )
    (comp (ref "R50")
      (value "10K")
      (footprint "eagle-import:R0603")
      (libsource (lib "eagle-import") (part "R-US_R0603"))
    )
    (comp (ref "R51")
      (value "10K")
      (footprint "eagle-import:R0603")
      (libsource (lib "eagle-import") (part "R-US_R0603"))
    )
    (comp (ref "R52")
      (value "10K")
      (footprint "eagle-import:R0603")
      (libsource (lib "eagle-import") (part "R-US_R0603"))
    )
    (comp (ref "U1")
      (value "AD8022ARMZ")
      (footprint "eagle-import:SOP65P490X110-8N")
      (libsource (lib "eagle-import") (part "AD8022ARMZ"))
    )
    (comp (ref "U8")
      (value "AD8022ARMZ")
      (footprint "eagle-import:SOP65P490X110-8N")
      (libsource (lib "eagle-import") (part "AD8022ARMZ"))
    )
    (comp (ref "U9")
      (value "AD8022ARMZ")
      (footprint "eagle-import:SOP65P490X110-8N")
      (libsource (lib "eagle-import") (part "AD8022ARMZ"))
    )
    (comp (ref "X1")
      (value "LTI-SASF54GT")
      (footprint "eagle-import:LTI-SASF54GT")
      (libsource (lib "eagle-import") (part "LTI-SASF54GT"))
    )
    (comp (ref "X2")
      (value "LTI-SASF54GT")
      (footprint "eagle-import:LTI-SASF54GT")
      (libsource (lib "eagle-import") (part "LTI-SASF54GT"))
    )
    (comp (ref "X11")
      (value "LTI-SASF54GT")
      (footprint "eagle-import:LTI-SASF54GT")
      (libsource (lib "eagle-import") (part "LTI-SASF54GT"))
    )
    (comp (ref "X12")
      (value "LTI-SASF54GT")
      (footprint "eagle-import:LTI-SASF54GT")
      (libsource (lib "eagle-import") (part "LTI-SASF54GT"))
    )
    (comp (ref "X13")
      (value "LTI-SASF54GT")
      (footprint "eagle-import:LTI-SASF54GT")
      (libsource (lib "eagle-import") (part "LTI-SASF54GT"))
    )
    (comp (ref "X14")
      (value "LTI-SASF54GT")
      (footprint "eagle-import:LTI-SASF54GT")
      (libsource (lib "eagle-import") (part "LTI-SASF54GT"))
    )
  )
  (nets
    (net (code "1") (name "+3V3") (class "Default")
      (node (ref "ADC1") (pin "16") (pinfunction "VDR_16") (pintype "power_in"))
      (node (ref "ADC2") (pin "16") (pinfunction "VDR_16") (pintype "power_in"))
      (node (ref "ADC3") (pin "16") (pinfunction "VDR_16") (pintype "power_in"))
      (node (ref "C10") (pin "1") (pinfunction "1_1") (pintype "passive"))
      (node (ref "C33") (pin "+") (pinfunction "+_+") (pintype "passive"))
      (node (ref "C34") (pin "1") (pinfunction "1_1") (pintype "passive"))
      (node (ref "C44") (pin "+") (pinfunction "+_+") (pintype "passive"))
      (node (ref "C45") (pin "1") (pinfunction "1_1") (pintype "passive"))
      (node (ref "C51") (pin "+") (pinfunction "+_+") (pintype "passive"))
      (node (ref "C52") (pin "1") (pinfunction "1_1") (pintype "passive"))
      (node (ref "C79") (pin "+") (pinfunction "+_+") (pintype "passive"))
      (node (ref "C80") (pin "1") (pinfunction "1_1") (pintype "passive"))
      (node (ref "C9") (pin "+") (pinfunction "+_+") (pintype "passive"))
      (node (ref "C99") (pin "1") (pinfunction "1_1") (pintype "passive"))
      (node (ref "U$3") (pin "7") (pinfunction "VOUT1_7") (pintype "passive"))
      (node (ref "U$3") (pin "8") (pinfunction "SENSE1_8") (pintype "passive"))
      (node (ref "U2") (pin "14") (pinfunction "DVCC_14") (pintype "power_in"))
      (node (ref "U6") (pin "14") (pinfunction "DVCC_14") (pintype "power_in"))
    )
    (net (code "2") (name "+5V") (class "Default")
      (node (ref "ADCOP1") (pin "3") (pinfunction "V+_3") (pintype "power_in"))
      (node (ref "ADCOP2") (pin "3") (pinfunction "V+_3") (pintype "power_in"))
      (node (ref "ADCOP3") (pin "3") (pinfunction "V+_3") (pintype "power_in"))
      (node (ref "ADCOP4") (pin "3") (pinfunction "V+_3") (pintype "power_in"))
      (node (ref "ADCOP5") (pin "3") (pinfunction "V+_3") (pintype "power_in"))
      (node (ref "ADCOP6") (pin "3") (pinfunction "V+_3") (pintype "power_in"))
      (node (ref "C14") (pin "2") (pinfunction "2_2") (pintype "passive"))
      (node (ref "C17") (pin "+") (pinfunction "+_+") (pintype "passive"))
      (node (ref "C18") (pin "2") (pinfunction "2_2") (pintype "passive"))
      (node (ref "C21") (pin "+") (pinfunction "+_+") (pintype "passive"))
      (node (ref "C22") (pin "2") (pinfunction "2_2") (pintype "passive"))
      (node (ref "C30") (pin "1") (pinfunction "1_1") (pintype "passive"))
      (node (ref "C32") (pin "1") (pinfunction "1_1") (pintype "passive"))
      (node (ref "C39") (pin "+") (pinfunction "+_+") (pintype "passive"))
      (node (ref "C40") (pin "2") (pinfunction "2_2") (pintype "passive"))
      (node (ref "C43") (pin "1") (pinfunction "1_1") (pintype "passive"))
      (node (ref "C58") (pin "+") (pinfunction "+_+") (pintype "passive"))
      (node (ref "C59") (pin "2") (pinfunction "2_2") (pintype "passive"))
      (node (ref "C62") (pin "+") (pinfunction "+_+") (pintype "passive"))
      (node (ref "C63") (pin "2") (pinfunction "2_2") (pintype "passive"))
      (node (ref "C66") (pin "+") (pinfunction "+_+") (pintype "passive"))
      (node (ref "C67") (pin "2") (pinfunction "2_2") (pintype "passive"))
      (node (ref "C7") (pin "+") (pinfunction "+_+") (pintype "passive"))
      (node (ref "C70") (pin "+") (pinfunction "+_+") (pintype "passive"))
      (node (ref "C71") (pin "2") (pinfunction "2_2") (pintype "passive"))
      (node (ref "C86") (pin "+") (pinfunction "+_+") (pintype "passive"))
      (node (ref "C87") (pin "2") (pinfunction "2_2") (pintype "passive"))
      (node (ref "C90") (pin "+") (pinfunction "+_+") (pintype "passive"))
      (node (ref "C91") (pin "2") (pinfunction "2_2") (pintype "passive"))
      (node (ref "C94") (pin "+") (pinfunction "+_+") (pintype "passive"))
      (node (ref "C95") (pin "2") (pinfunction "2_2") (pintype "passive"))
      (node (ref "U$3") (pin "1") (pinfunction "EN1_1") (pintype "passive"))
      (node (ref "U$3") (pin "2") (pinfunction "EN2_2") (pintype "passive"))
      (node (ref "U$3") (pin "6") (pinfunction "VIN_6") (pintype "passive"))
      (node (ref "U$7") (pin "OUT") (pinfunction "3_OUT") (pintype "passive"))
      (node (ref "U$8") (pin "1") (pinfunction "1_1") (pintype "bidirectional"))
      (node (ref "U1") (pin "8") (pinfunction "+VS_8") (pintype "power_in"))
      (node (ref "U2") (pin "24") (pinfunction "AVDD_24") (pintype "power_in"))
      (node (ref "U3") (pin "2") (pinfunction "VIN_2") (pintype "power_in"))
      (node (ref "U6") (pin "24") (pinfunction "AVDD_24") (pintype "power_in"))
      (node (ref "U7") (pin "2") (pinfunction "VIN_2") (pintype "power_in"))
      (node (ref "U8") (pin "8") (pinfunction "+VS_8") (pintype "power_in"))
      (node (ref "U9") (pin "8") (pinfunction "+VS_8") (pintype "power_in"))
    )
    (net (code "3") (name "-5V") (class "Default")
      (node (ref "ADCOP1") (pin "6") (pinfunction "V-_6") (pintype "power_in"))
      (node (ref "ADCOP2") (pin "6") (pinfunction "V-_6") (pintype "power_in"))
      (node (ref "ADCOP3") (pin "6") (pinfunction "V-_6") (pintype "power_in"))
      (node (ref "ADCOP4") (pin "6") (pinfunction "V-_6") (pintype "power_in"))
      (node (ref "ADCOP5") (pin "6") (pinfunction "V-_6") (pintype "power_in"))
      (node (ref "ADCOP6") (pin "6") (pinfunction "V-_6") (pintype "power_in"))
      (node (ref "C15") (pin "-") (pinfunction "-_-") (pintype "passive"))
      (node (ref "C16") (pin "2") (pinfunction "2_2") (pintype "passive"))
      (node (ref "C19") (pin "-") (pinfunction "-_-") (pintype "passive"))
      (node (ref "C20") (pin "2") (pinfunction "2_2") (pintype "passive"))
      (node (ref "C23") (pin "-") (pinfunction "-_-") (pintype "passive"))
      (node (ref "C24") (pin "2") (pinfunction "2_2") (pintype "passive"))
      (node (ref "C41") (pin "-") (pinfunction "-_-") (pintype "passive"))
      (node (ref "C42") (pin "2") (pinfunction "2_2") (pintype "passive"))
      (node (ref "C60") (pin "-") (pinfunction "-_-") (pintype "passive"))
      (node (ref "C61") (pin "2") (pinfunction "2_2") (pintype "passive"))
      (node (ref "C64") (pin "-") (pinfunction "-_-") (pintype "passive"))
      (node (ref "C65") (pin "2") (pinfunction "2_2") (pintype "passive"))
      (node (ref "C68") (pin "-") (pinfunction "-_-") (pintype "passive"))
      (node (ref "C69") (pin "2") (pinfunction "2_2") (pintype "passive"))
      (node (ref "C72") (pin "-") (pinfunction "-_-") (pintype "passive"))
      (node (ref "C73") (pin "2") (pinfunction "2_2") (pintype "passive"))
      (node (ref "C88") (pin "-") (pinfunction "-_-") (pintype "passive"))
      (node (ref "C89") (pin "2") (pinfunction "2_2") (pintype "passive"))
      (node (ref "C92") (pin "-") (pinfunction "-_-") (pintype "passive"))
      (node (ref "C93") (pin "2") (pinfunction "2_2") (pintype "passive"))
      (node (ref "C96") (pin "-") (pinfunction "-_-") (pintype "passive"))
      (node (ref "C97") (pin "2") (pinfunction "2_2") (pintype "passive"))
      (node (ref "U$6") (pin "OUT") (pinfunction "3_OUT") (pintype "passive"))
      (node (ref "U$8") (pin "3") (pinfunction "3_3") (pintype "bidirectional"))
      (node (ref "U1") (pin "4") (pinfunction "-VS_4") (pintype "power_in"))
      (node (ref "U2") (pin "1") (pinfunction "AVSS_1") (pintype "passive"))
      (node (ref "U6") (pin "1") (pinfunction "AVSS_1") (pintype "passive"))
      (node (ref "U8") (pin "4") (pinfunction "-VS_4") (pintype "power_in"))
      (node (ref "U9") (pin "4") (pinfunction "-VS_4") (pintype "power_in"))
    )
    (net (code "4") (name "ADC0") (class "Default")
      (node (ref "ADC1") (pin "10") (pinfunction "~{CS}_10") (pintype "input"))
      (node (ref "J1") (pin "266") (pinfunction "P$66_266") (pintype "bidirectional"))
    )
    (net (code "5") (name "ADC1") (class "Default")
      (node (ref "ADC1") (pin "13") (pinfunction "SDATAB_13") (pintype "output"))
      (node (ref "J1") (pin "264") (pinfunction "P$64_264") (pintype "bidirectional"))
    )
    (net (code "6") (name "ADC2") (class "Default")
      (node (ref "ADC1") (pin "14") (pinfunction "SDATAA_14") (pintype "output"))
      (node (ref "J1") (pin "262") (pinfunction "P$62_262") (pintype "bidirectional"))
    )
    (net (code "7") (name "ADC3") (class "Default")
      (node (ref "ADC1") (pin "15") (pinfunction "SCLK_15") (pintype "input"))
      (node (ref "J1") (pin "260") (pinfunction "P$60_260") (pintype "bidirectional"))
    )
    (net (code "8") (name "ADC7") (class "Default")
      (node (ref "ADC2") (pin "10") (pinfunction "~{CS}_10") (pintype "input"))
      (node (ref "J1") (pin "222") (pinfunction "P$22_222") (pintype "bidirectional"))
    )
    (net (code "9") (name "ADC8") (class "Default")
      (node (ref "ADC2") (pin "13") (pinfunction "SDATAB_13") (pintype "output"))
      (node (ref "J1") (pin "220") (pinfunction "P$20_220") (pintype "bidirectional"))
    )
    (net (code "10") (name "ADC9") (class "Default")
      (node (ref "ADC2") (pin "14") (pinfunction "SDATAA_14") (pintype "output"))
      (node (ref "J1") (pin "218") (pinfunction "P$18_218") (pintype "bidirectional"))
    )
    (net (code "11") (name "ADC10") (class "Default")
      (node (ref "ADC2") (pin "15") (pinfunction "SCLK_15") (pintype "input"))
      (node (ref "J1") (pin "216") (pinfunction "P$16_216") (pintype "bidirectional"))
    )
    (net (code "12") (name "ADC11") (class "Default")
      (node (ref "ADC3") (pin "10") (pinfunction "~{CS}_10") (pintype "input"))
      (node (ref "J1") (pin "221") (pinfunction "P$21_221") (pintype "bidirectional"))
    )
    (net (code "13") (name "ADC12") (class "Default")
      (node (ref "ADC3") (pin "13") (pinfunction "SDATAB_13") (pintype "output"))
      (node (ref "J1") (pin "219") (pinfunction "P$19_219") (pintype "bidirectional"))
    )
    (net (code "14") (name "ADC13") (class "Default")
      (node (ref "ADC3") (pin "14") (pinfunction "SDATAA_14") (pintype "output"))
      (node (ref "J1") (pin "217") (pinfunction "P$17_217") (pintype "bidirectional"))
    )
    (net (code "15") (name "ADC14") (class "Default")
      (node (ref "ADC3") (pin "15") (pinfunction "SCLK_15") (pintype "input"))
      (node (ref "J1") (pin "215") (pinfunction "P$15_215") (pintype "bidirectional"))
    )
    (net (code "16") (name "DACD0") (class "Default")
      (node (ref "J1") (pin "268") (pinfunction "P$68_268") (pintype "bidirectional"))
      (node (ref "U2") (pin "7") (pinfunction "SYNC_7") (pintype "passive"))
    )
    (net (code "17") (name "DACD1") (class "Default")
      (node (ref "J1") (pin "270") (pinfunction "P$70_270") (pintype "bidirectional"))
      (node (ref "U2") (pin "8") (pinfunction "SCLK_8") (pintype "passive"))
    )
    (net (code "18") (name "DACD2") (class "Default")
      (node (ref "J1") (pin "272") (pinfunction "P$72_272") (pintype "bidirectional"))
      (node (ref "U2") (pin "9") (pinfunction "SDIN_9") (pintype "passive"))
    )
    (net (code "19") (name "DACD3") (class "Default")
      (node (ref "J1") (pin "274") (pinfunction "P$74_274") (pintype "bidirectional"))
      (node (ref "U2") (pin "10") (pinfunction "LDAC_10") (pintype "passive"))
    )
    (net (code "20") (name "DACD4") (class "Default")
      (node (ref "J1") (pin "276") (pinfunction "P$76_276") (pintype "bidirectional"))
      (node (ref "U2") (pin "11") (pinfunction "CLR_11") (pintype "passive"))
    )
    (net (code "21") (name "DACD5") (class "Default")
      (node (ref "J1") (pin "267") (pinfunction "P$67_267") (pintype "bidirectional"))
      (node (ref "U6") (pin "7") (pinfunction "SYNC_7") (pintype "passive"))
    )
    (net (code "22") (name "DACD6") (class "Default")
      (node (ref "J1") (pin "269") (pinfunction "P$69_269") (pintype "bidirectional"))
      (node (ref "U6") (pin "8") (pinfunction "SCLK_8") (pintype "passive"))
    )
    (net (code "23") (name "DACD7") (class "Default")
      (node (ref "J1") (pin "271") (pinfunction "P$71_271") (pintype "bidirectional"))
      (node (ref "U6") (pin "9") (pinfunction "SDIN_9") (pintype "passive"))
    )
    (net (code "24") (name "DACD8") (class "Default")
      (node (ref "J1") (pin "273") (pinfunction "P$73_273") (pintype "bidirectional"))
      (node (ref "U6") (pin "10") (pinfunction "LDAC_10") (pintype "passive"))
    )
    (net (code "25") (name "DACD9") (class "Default")
      (node (ref "J1") (pin "275") (pinfunction "P$75_275") (pintype "bidirectional"))
      (node (ref "U6") (pin "11") (pinfunction "CLR_11") (pintype "passive"))
    )
    (net (code "26") (name "GND") (class "Default")
      (node (ref "ADC1") (pin "11") (pinfunction "AGND_11") (pintype "passive"))
      (node (ref "ADC1") (pin "12") (pinfunction "DGND_12") (pintype "passive"))
      (node (ref "ADC1") (pin "4") (pinfunction "REFGND_4") (pintype "passive"))
      (node (ref "ADC1") (pin "5") (pinfunction "AGND_2_5") (pintype "passive"))
      (node (ref "ADC2") (pin "11") (pinfunction "AGND_11") (pintype "passive"))
      (node (ref "ADC2") (pin "12") (pinfunction "DGND_12") (pintype "passive"))
      (node (ref "ADC2") (pin "4") (pinfunction "REFGND_4") (pintype "passive"))
      (node (ref "ADC2") (pin "5") (pinfunction "AGND_2_5") (pintype "passive"))
      (node (ref "ADC3") (pin "11") (pinfunction "AGND_11") (pintype "passive"))
      (node (ref "ADC3") (pin "12") (pinfunction "DGND_12") (pintype "passive"))
      (node (ref "ADC3") (pin "4") (pinfunction "REFGND_4") (pintype "passive"))
      (node (ref "ADC3") (pin "5") (pinfunction "AGND_2_5") (pintype "passive"))
      (node (ref "C10") (pin "2") (pinfunction "2_2") (pintype "passive"))
      (node (ref "C100") (pin "2") (pinfunction "2_2") (pintype "passive"))
      (node (ref "C11") (pin "2") (pinfunction "2_2") (pintype "passive"))
      (node (ref "C12") (pin "-") (pinfunction "-_-") (pintype "passive"))
      (node (ref "C13") (pin "-") (pinfunction "-_-") (pintype "passive"))
      (node (ref "C14") (pin "1") (pinfunction "1_1") (pintype "passive"))
      (node (ref "C15") (pin "+") (pinfunction "+_+") (pintype "passive"))
      (node (ref "C16") (pin "1") (pinfunction "1_1") (pintype "passive"))
      (node (ref "C17") (pin "-") (pinfunction "-_-") (pintype "passive"))
      (node (ref "C18") (pin "1") (pinfunction "1_1") (pintype "passive"))
      (node (ref "C19") (pin "+") (pinfunction "+_+") (pintype "passive"))
      (node (ref "C20") (pin "1") (pinfunction "1_1") (pintype "passive"))
      (node (ref "C21") (pin "-") (pinfunction "-_-") (pintype "passive"))
      (node (ref "C22") (pin "1") (pinfunction "1_1") (pintype "passive"))
      (node (ref "C23") (pin "+") (pinfunction "+_+") (pintype "passive"))
      (node (ref "C24") (pin "1") (pinfunction "1_1") (pintype "passive"))
      (node (ref "C25") (pin "1") (pinfunction "1_1") (pintype "passive"))
      (node (ref "C26") (pin "2") (pinfunction "2_2") (pintype "passive"))
      (node (ref "C27") (pin "2") (pinfunction "2_2") (pintype "passive"))
      (node (ref "C28") (pin "2") (pinfunction "2_2") (pintype "passive"))
      (node (ref "C29") (pin "-") (pinfunction "-_-") (pintype "passive"))
      (node (ref "C3") (pin "2") (pinfunction "2_2") (pintype "passive"))
      (node (ref "C30") (pin "2") (pinfunction "2_2") (pintype "passive"))
      (node (ref "C32") (pin "2") (pinfunction "2_2") (pintype "passive"))
      (node (ref "C33") (pin "-") (pinfunction "-_-") (pintype "passive"))
      (node (ref "C34") (pin "2") (pinfunction "2_2") (pintype "passive"))
      (node (ref "C35") (pin "-") (pinfunction "-_-") (pintype "passive"))
      (node (ref "C36") (pin "-") (pinfunction "-_-") (pintype "passive"))
      (node (ref "C37") (pin "1") (pinfunction "1_1") (pintype "passive"))
      (node (ref "C38") (pin "1") (pinfunction "1_1") (pintype "passive"))
      (node (ref "C39") (pin "-") (pinfunction "-_-") (pintype "passive"))
      (node (ref "C40") (pin "1") (pinfunction "1_1") (pintype "passive"))
      (node (ref "C41") (pin "+") (pinfunction "+_+") (pintype "passive"))
      (node (ref "C42") (pin "1") (pinfunction "1_1") (pintype "passive"))
      (node (ref "C43") (pin "2") (pinfunction "2_2") (pintype "passive"))
      (node (ref "C44") (pin "-") (pinfunction "-_-") (pintype "passive"))
      (node (ref "C45") (pin "2") (pinfunction "2_2") (pintype "passive"))
      (node (ref "C50") (pin "-") (pinfunction "-_-") (pintype "passive"))
      (node (ref "C51") (pin "-") (pinfunction "-_-") (pintype "passive"))
      (node (ref "C52") (pin "2") (pinfunction "2_2") (pintype "passive"))
      (node (ref "C53") (pin "2") (pinfunction "2_2") (pintype "passive"))
      (node (ref "C54") (pin "-") (pinfunction "-_-") (pintype "passive"))
      (node (ref "C55") (pin "-") (pinfunction "-_-") (pintype "passive"))
      (node (ref "C56") (pin "2") (pinfunction "2_2") (pintype "passive"))
      (node (ref "C57") (pin "1") (pinfunction "1_1") (pintype "passive"))
      (node (ref "C58") (pin "-") (pinfunction "-_-") (pintype "passive"))
      (node (ref "C59") (pin "1") (pinfunction "1_1") (pintype "passive"))
      (node (ref "C6") (pin "1") (pinfunction "1_1") (pintype "passive"))
      (node (ref "C60") (pin "+") (pinfunction "+_+") (pintype "passive"))
      (node (ref "C61") (pin "1") (pinfunction "1_1") (pintype "passive"))
      (node (ref "C62") (pin "-") (pinfunction "-_-") (pintype "passive"))
      (node (ref "C63") (pin "1") (pinfunction "1_1") (pintype "passive"))
      (node (ref "C64") (pin "+") (pinfunction "+_+") (pintype "passive"))
      (node (ref "C65") (pin "1") (pinfunction "1_1") (pintype "passive"))
      (node (ref "C66") (pin "-") (pinfunction "-_-") (pintype "passive"))
      (node (ref "C67") (pin "1") (pinfunction "1_1") (pintype "passive"))
      (node (ref "C68") (pin "+") (pinfunction "+_+") (pintype "passive"))
      (node (ref "C69") (pin "1") (pinfunction "1_1") (pintype "passive"))
      (node (ref "C7") (pin "-") (pinfunction "-_-") (pintype "passive"))
      (node (ref "C70") (pin "-") (pinfunction "-_-") (pintype "passive"))
      (node (ref "C71") (pin "1") (pinfunction "1_1") (pintype "passive"))
      (node (ref "C72") (pin "+") (pinfunction "+_+") (pintype "passive"))
      (node (ref "C73") (pin "1") (pinfunction "1_1") (pintype "passive"))
      (node (ref "C78") (pin "-") (pinfunction "-_-") (pintype "passive"))
      (node (ref "C79") (pin "-") (pinfunction "-_-") (pintype "passive"))
      (node (ref "C8") (pin "-") (pinfunction "-_-") (pintype "passive"))
      (node (ref "C80") (pin "2") (pinfunction "2_2") (pintype "passive"))
      (node (ref "C81") (pin "2") (pinfunction "2_2") (pintype "passive"))
      (node (ref "C82") (pin "-") (pinfunction "-_-") (pintype "passive"))
      (node (ref "C83") (pin "-") (pinfunction "-_-") (pintype "passive"))
      (node (ref "C84") (pin "2") (pinfunction "2_2") (pintype "passive"))
      (node (ref "C85") (pin "1") (pinfunction "1_1") (pintype "passive"))
      (node (ref "C86") (pin "-") (pinfunction "-_-") (pintype "passive"))
      (node (ref "C87") (pin "1") (pinfunction "1_1") (pintype "passive"))
      (node (ref "C88") (pin "+") (pinfunction "+_+") (pintype "passive"))
      (node (ref "C89") (pin "1") (pinfunction "1_1") (pintype "passive"))
      (node (ref "C9") (pin "-") (pinfunction "-_-") (pintype "passive"))
      (node (ref "C90") (pin "-") (pinfunction "-_-") (pintype "passive"))
      (node (ref "C91") (pin "1") (pinfunction "1_1") (pintype "passive"))
      (node (ref "C92") (pin "+") (pinfunction "+_+") (pintype "passive"))
      (node (ref "C93") (pin "1") (pinfunction "1_1") (pintype "passive"))
      (node (ref "C94") (pin "-") (pinfunction "-_-") (pintype "passive"))
      (node (ref "C95") (pin "1") (pinfunction "1_1") (pintype "passive"))
      (node (ref "C96") (pin "+") (pinfunction "+_+") (pintype "passive"))
      (node (ref "C97") (pin "1") (pinfunction "1_1") (pintype "passive"))
      (node (ref "C98") (pin "+") (pinfunction "+_+") (pintype "passive"))
      (node (ref "C99") (pin "2") (pinfunction "2_2") (pintype "passive"))
      (node (ref "J1") (pin "102") (pinfunction "P$102_102") (pintype "bidirectional"))
      (node (ref "J1") (pin "114") (pinfunction "P$114_114") (pintype "bidirectional"))
      (node (ref "J1") (pin "135") (pinfunction "P$135_135") (pintype "bidirectional"))
      (node (ref "J1") (pin "155") (pinfunction "P$155_155") (pintype "bidirectional"))
      (node (ref "J1") (pin "178") (pinfunction "P$178_178") (pintype "bidirectional"))
      (node (ref "J1") (pin "180") (pinfunction "P$180_180") (pintype "bidirectional"))
      (node (ref "J1") (pin "201") (pinfunction "P$1_201") (pintype "bidirectional"))
      (node (ref "J1") (pin "213") (pinfunction "P$13_213") (pintype "bidirectional"))
      (node (ref "J1") (pin "214") (pinfunction "P$14_214") (pintype "bidirectional"))
      (node (ref "J1") (pin "236") (pinfunction "P$36_236") (pintype "bidirectional"))
      (node (ref "J1") (pin "256") (pinfunction "P$56_256") (pintype "bidirectional"))
      (node (ref "J1") (pin "278") (pinfunction "P$78_278") (pintype "bidirectional"))
      (node (ref "J1") (pin "280") (pinfunction "P$80_280") (pintype "bidirectional"))
      (node (ref "R14") (pin "1") (pinfunction "1_1") (pintype "passive"))
      (node (ref "R16") (pin "1") (pinfunction "1_1") (pintype "passive"))
      (node (ref "R17") (pin "1") (pinfunction "1_1") (pintype "passive"))
      (node (ref "R19") (pin "1") (pinfunction "1_1") (pintype "passive"))
      (node (ref "R25") (pin "1") (pinfunction "1_1") (pintype "passive"))
      (node (ref "R31") (pin "1") (pinfunction "1_1") (pintype "passive"))
      (node (ref "R35") (pin "2") (pinfunction "2_2") (pintype "passive"))
      (node (ref "R36") (pin "1") (pinfunction "1_1") (pintype "passive"))
      (node (ref "R41") (pin "1") (pinfunction "1_1") (pintype "passive"))
      (node (ref "R47") (pin "1") (pinfunction "1_1") (pintype "passive"))
      (node (ref "R5") (pin "1") (pinfunction "1_1") (pintype "passive"))
      (node (ref "R51") (pin "2") (pinfunction "2_2") (pintype "passive"))
      (node (ref "R52") (pin "1") (pinfunction "1_1") (pintype "passive"))
      (node (ref "R9") (pin "2") (pinfunction "2_2") (pintype "passive"))
      (node (ref "U$1") (pin "A4") (pinfunction "VOUT-_A4") (pintype "bidirectional"))
      (node (ref "U$1") (pin "A5") (pinfunction "VOUT-_A5") (pintype "bidirectional"))
      (node (ref "U$1") (pin "B3") (pinfunction "GND_B3") (pintype "bidirectional"))
      (node (ref "U$1") (pin "B4") (pinfunction "VOUT-_B4") (pintype "bidirectional"))
      (node (ref "U$1") (pin "B5") (pinfunction "VOUT-_B5") (pintype "bidirectional"))
      (node (ref "U$1") (pin "C1") (pinfunction "GND_C1") (pintype "bidirectional"))
      (node (ref "U$1") (pin "C2") (pinfunction "GND_C2") (pintype "bidirectional"))
      (node (ref "U$1") (pin "C3") (pinfunction "GND_C3") (pintype "bidirectional"))
      (node (ref "U$1") (pin "C4") (pinfunction "GND_C4") (pintype "bidirectional"))
      (node (ref "U$1") (pin "C5") (pinfunction "GND_C5") (pintype "bidirectional"))
      (node (ref "U$1") (pin "D1") (pinfunction "GND_D1") (pintype "bidirectional"))
      (node (ref "U$1") (pin "D2") (pinfunction "GND_D2") (pintype "bidirectional"))
      (node (ref "U$1") (pin "D3") (pinfunction "GND_D3") (pintype "bidirectional"))
      (node (ref "U$1") (pin "D4") (pinfunction "GND_D4") (pintype "bidirectional"))
      (node (ref "U$1") (pin "D5") (pinfunction "GND_D5") (pintype "bidirectional"))
      (node (ref "U$1") (pin "E1") (pinfunction "SYNC_E1") (pintype "bidirectional"))
      (node (ref "U$1") (pin "E2") (pinfunction "GND_E2") (pintype "bidirectional"))
      (node (ref "U$1") (pin "E3") (pinfunction "GND_E3") (pintype "bidirectional"))
      (node (ref "U$1") (pin "E4") (pinfunction "GND_E4") (pintype "bidirectional"))
      (node (ref "U$1") (pin "E5") (pinfunction "GND_E5") (pintype "bidirectional"))
      (node (ref "U$1") (pin "F2") (pinfunction "GND_F2") (pintype "bidirectional"))
      (node (ref "U$1") (pin "F3") (pinfunction "GND_F3") (pintype "bidirectional"))
      (node (ref "U$1") (pin "F4") (pinfunction "GND_F4") (pintype "bidirectional"))
      (node (ref "U$1") (pin "F5") (pinfunction "GND_F5") (pintype "bidirectional"))
      (node (ref "U$1") (pin "G2") (pinfunction "GND_G2") (pintype "bidirectional"))
      (node (ref "U$1") (pin "H1") (pinfunction "GND_H1") (pintype "bidirectional"))
      (node (ref "U$1") (pin "H2") (pinfunction "GND_H2") (pintype "bidirectional"))
      (node (ref "U$1") (pin "H3") (pinfunction "GND_H3") (pintype "bidirectional"))
      (node (ref "U$2") (pin "A1") (pinfunction "VOUT+_A1") (pintype "bidirectional"))
      (node (ref "U$2") (pin "A2") (pinfunction "VOUT+_A2") (pintype "bidirectional"))
      (node (ref "U$2") (pin "B1") (pinfunction "VOUT+_B1") (pintype "bidirectional"))
      (node (ref "U$2") (pin "B2") (pinfunction "VOUT+_B2") (pintype "bidirectional"))
      (node (ref "U$2") (pin "B3") (pinfunction "GND_B3") (pintype "bidirectional"))
      (node (ref "U$2") (pin "C1") (pinfunction "GND_C1") (pintype "bidirectional"))
      (node (ref "U$2") (pin "C2") (pinfunction "GND_C2") (pintype "bidirectional"))
      (node (ref "U$2") (pin "C3") (pinfunction "GND_C3") (pintype "bidirectional"))
      (node (ref "U$2") (pin "C4") (pinfunction "GND_C4") (pintype "bidirectional"))
      (node (ref "U$2") (pin "C5") (pinfunction "GND_C5") (pintype "bidirectional"))
      (node (ref "U$2") (pin "D1") (pinfunction "GND_D1") (pintype "bidirectional"))
      (node (ref "U$2") (pin "D2") (pinfunction "GND_D2") (pintype "bidirectional"))
      (node (ref "U$2") (pin "D3") (pinfunction "GND_D3") (pintype "bidirectional"))
      (node (ref "U$2") (pin "D4") (pinfunction "GND_D4") (pintype "bidirectional"))
      (node (ref "U$2") (pin "D5") (pinfunction "GND_D5") (pintype "bidirectional"))
      (node (ref "U$2") (pin "E1") (pinfunction "SYNC_E1") (pintype "bidirectional"))
      (node (ref "U$2") (pin "E2") (pinfunction "GND_E2") (pintype "bidirectional"))
      (node (ref "U$2") (pin "E3") (pinfunction "GND_E3") (pintype "bidirectional"))
      (node (ref "U$2") (pin "E4") (pinfunction "GND_E4") (pintype "bidirectional"))
      (node (ref "U$2") (pin "E5") (pinfunction "GND_E5") (pintype "bidirectional"))
      (node (ref "U$2") (pin "F2") (pinfunction "GND_F2") (pintype "bidirectional"))
      (node (ref "U$2") (pin "F3") (pinfunction "GND_F3") (pintype "bidirectional"))
      (node (ref "U$2") (pin "F4") (pinfunction "GND_F4") (pintype "bidirectional"))
      (node (ref "U$2") (pin "F5") (pinfunction "GND_F5") (pintype "bidirectional"))
      (node (ref "U$2") (pin "G2") (pinfunction "GND_G2") (pintype "bidirectional"))
      (node (ref "U$2") (pin "H1") (pinfunction "GND_H1") (pintype "bidirectional"))
      (node (ref "U$2") (pin "H2") (pinfunction "GND_H2") (pintype "bidirectional"))
      (node (ref "U$2") (pin "H3") (pinfunction "GND_H3") (pintype "bidirectional"))
      (node (ref "U$3") (pin "3") (pinfunction "GND_3") (pintype "passive"))
      (node (ref "U$3") (pin "9") (pinfunction "EP_9") (pintype "passive"))
      (node (ref "U$4") (pin "GND") (pinfunction "2_GND") (pintype "passive"))
      (node (ref "U$4") (pin "GND2") (pinfunction "2_GND2") (pintype "passive"))
      (node (ref "U$5") (pin "GND") (pinfunction "2_GND") (pintype "passive"))
      (node (ref "U$5") (pin "GND2") (pinfunction "2_GND2") (pintype "passive"))
      (node (ref "U$6") (pin "GND") (pinfunction "2_GND") (pintype "passive"))
      (node (ref "U$6") (pin "GND2") (pinfunction "2_GND2") (pintype "passive"))
      (node (ref "U$7") (pin "GND") (pinfunction "2_GND") (pintype "passive"))
      (node (ref "U$7") (pin "GND2") (pinfunction "2_GND2") (pintype "passive"))
      (node (ref "U$8") (pin "2") (pinfunction "2_2") (pintype "bidirectional"))
      (node (ref "U2") (pin "15") (pinfunction "GND_15") (pintype "passive"))
      (node (ref "U2") (pin "18") (pinfunction "DAC_GND_18") (pintype "passive"))
      (node (ref "U2") (pin "19") (pinfunction "DAC_GND_2_19") (pintype "passive"))
      (node (ref "U2") (pin "20") (pinfunction "SIG_GND_20") (pintype "passive"))
      (node (ref "U2") (pin "21") (pinfunction "SIG_GND_2_21") (pintype "passive"))
      (node (ref "U2") (pin "5") (pinfunction "BIN/_2SCOMP_5") (pintype "passive"))
      (node (ref "U3") (pin "4") (pinfunction "GND_4") (pintype "passive"))
      (node (ref "U4") (pin "5") (pinfunction "GND_5") (pintype "passive"))
      (node (ref "U5") (pin "3") (pinfunction "GND_2_3") (pintype "passive"))
      (node (ref "U5") (pin "6") (pinfunction "GND_6") (pintype "passive"))
      (node (ref "U5") (pin "7") (pinfunction "GND_3_7") (pintype "passive"))
      (node (ref "U6") (pin "15") (pinfunction "GND_15") (pintype "passive"))
      (node (ref "U6") (pin "18") (pinfunction "DAC_GND_18") (pintype "passive"))
      (node (ref "U6") (pin "19") (pinfunction "DAC_GND_2_19") (pintype "passive"))
      (node (ref "U6") (pin "20") (pinfunction "SIG_GND_20") (pintype "passive"))
      (node (ref "U6") (pin "21") (pinfunction "SIG_GND_2_21") (pintype "passive"))
      (node (ref "U6") (pin "5") (pinfunction "BIN/_2SCOMP_5") (pintype "passive"))
      (node (ref "U7") (pin "4") (pinfunction "GND_4") (pintype "passive"))
      (node (ref "X1") (pin "2") (pinfunction "2_2") (pintype "passive"))
      (node (ref "X1") (pin "3") (pinfunction "2_3") (pintype "passive"))
      (node (ref "X1") (pin "4") (pinfunction "2_4") (pintype "passive"))
      (node (ref "X1") (pin "5") (pinfunction "2_5") (pintype "passive"))
      (node (ref "X10") (pin "2") (pinfunction "2_2") (pintype "passive"))
      (node (ref "X10") (pin "3") (pinfunction "2_3") (pintype "passive"))
      (node (ref "X10") (pin "4") (pinfunction "2_4") (pintype "passive"))
      (node (ref "X10") (pin "5") (pinfunction "2_5") (pintype "passive"))
      (node (ref "X11") (pin "2") (pinfunction "2_2") (pintype "passive"))
      (node (ref "X11") (pin "3") (pinfunction "2_3") (pintype "passive"))
      (node (ref "X11") (pin "4") (pinfunction "2_4") (pintype "passive"))
      (node (ref "X11") (pin "5") (pinfunction "2_5") (pintype "passive"))
      (node (ref "X12") (pin "2") (pinfunction "2_2") (pintype "passive"))
      (node (ref "X12") (pin "3") (pinfunction "2_3") (pintype "passive"))
      (node (ref "X12") (pin "4") (pinfunction "2_4") (pintype "passive"))
      (node (ref "X12") (pin "5") (pinfunction "2_5") (pintype "passive"))
      (node (ref "X13") (pin "2") (pinfunction "2_2") (pintype "passive"))
      (node (ref "X13") (pin "3") (pinfunction "2_3") (pintype "passive"))
      (node (ref "X13") (pin "4") (pinfunction "2_4") (pintype "passive"))
      (node (ref "X13") (pin "5") (pinfunction "2_5") (pintype "passive"))
      (node (ref "X14") (pin "2") (pinfunction "2_2") (pintype "passive"))
      (node (ref "X14") (pin "3") (pinfunction "2_3") (pintype "passive"))
      (node (ref "X14") (pin "4") (pinfunction "2_4") (pintype "passive"))
      (node (ref "X14") (pin "5") (pinfunction "2_5") (pintype "passive"))
      (node (ref "X2") (pin "2") (pinfunction "2_2") (pintype "passive"))
      (node (ref "X2") (pin "3") (pinfunction "2_3") (pintype "passive"))
      (node (ref "X2") (pin "4") (pinfunction "2_4") (pintype "passive"))
      (node (ref "X2") (pin "5") (pinfunction "2_5") (pintype "passive"))
      (node (ref "X3") (pin "2") (pinfunction "2_2") (pintype "passive"))
      (node (ref "X3") (pin "3") (pinfunction "2_3") (pintype "passive"))
      (node (ref "X3") (pin "4") (pinfunction "2_4") (pintype "passive"))
      (node (ref "X3") (pin "5") (pinfunction "2_5") (pintype "passive"))
      (node (ref "X4") (pin "2") (pinfunction "2_2") (pintype "passive"))
      (node (ref "X4") (pin "3") (pinfunction "2_3") (pintype "passive"))
      (node (ref "X4") (pin "4") (pinfunction "2_4") (pintype "passive"))
      (node (ref "X4") (pin "5") (pinfunction "2_5") (pintype "passive"))
      (node (ref "X5") (pin "2") (pinfunction "2_2") (pintype "passive"))
      (node (ref "X5") (pin "3") (pinfunction "2_3") (pintype "passive"))
      (node (ref "X5") (pin "4") (pinfunction "2_4") (pintype "passive"))
      (node (ref "X5") (pin "5") (pinfunction "2_5") (pintype "passive"))
      (node (ref "X6") (pin "2") (pinfunction "2_2") (pintype "passive"))
      (node (ref "X6") (pin "3") (pinfunction "2_3") (pintype "passive"))
      (node (ref "X6") (pin "4") (pinfunction "2_4") (pintype "passive"))
      (node (ref "X6") (pin "5") (pinfunction "2_5") (pintype "passive"))
      (node (ref "X7") (pin "2") (pinfunction "2_2") (pintype "passive"))
      (node (ref "X7") (pin "3") (pinfunction "2_3") (pintype "passive"))
      (node (ref "X7") (pin "4") (pinfunction "2_4") (pintype "passive"))
      (node (ref "X7") (pin "5") (pinfunction "2_5") (pintype "passive"))
      (node (ref "X8") (pin "2") (pinfunction "2_2") (pintype "passive"))
      (node (ref "X8") (pin "3") (pinfunction "2_3") (pintype "passive"))
      (node (ref "X8") (pin "4") (pinfunction "2_4") (pintype "passive"))
      (node (ref "X8") (pin "5") (pinfunction "2_5") (pintype "passive"))
      (node (ref "X9") (pin "2") (pinfunction "2_2") (pintype "passive"))
      (node (ref "X9") (pin "3") (pinfunction "2_3") (pintype "passive"))
      (node (ref "X9") (pin "4") (pinfunction "2_4") (pintype "passive"))
      (node (ref "X9") (pin "5") (pinfunction "2_5") (pintype "passive"))
    )
    (net (code "27") (name "Net-(ADC1-VINA+)") (class "Default")
      (node (ref "ADC1") (pin "1") (pinfunction "VINA+_1") (pintype "input"))
      (node (ref "R1") (pin "2") (pinfunction "2_2") (pintype "passive"))
    )
    (net (code "28") (name "Net-(ADC1-VINA-)") (class "Default")
      (node (ref "ADC1") (pin "2") (pinfunction "VINA-_2") (pintype "input"))
      (node (ref "R2") (pin "2") (pinfunction "2_2") (pintype "passive"))
    )
    (net (code "29") (name "Net-(ADC1-VINB+)") (class "Default")
      (node (ref "ADC1") (pin "8") (pinfunction "VINB+_8") (pintype "input"))
      (node (ref "R10") (pin "2") (pinfunction "2_2") (pintype "passive"))
    )
    (net (code "30") (name "Net-(ADC1-VINB-)") (class "Default")
      (node (ref "ADC1") (pin "7") (pinfunction "VINB-_7") (pintype "input"))
      (node (ref "R11") (pin "2") (pinfunction "2_2") (pintype "passive"))
    )
    (net (code "31") (name "Net-(ADC2-VINA+)") (class "Default")
      (node (ref "ADC2") (pin "1") (pinfunction "VINA+_1") (pintype "input"))
      (node (ref "R21") (pin "2") (pinfunction "2_2") (pintype "passive"))
    )
    (net (code "32") (name "Net-(ADC2-VINA-)") (class "Default")
      (node (ref "ADC2") (pin "2") (pinfunction "VINA-_2") (pintype "input"))
      (node (ref "R22") (pin "2") (pinfunction "2_2") (pintype "passive"))
    )
    (net (code "33") (name "Net-(ADC2-VINB+)") (class "Default")
      (node (ref "ADC2") (pin "8") (pinfunction "VINB+_8") (pintype "input"))
      (node (ref "R27") (pin "2") (pinfunction "2_2") (pintype "passive"))
    )
    (net (code "34") (name "Net-(ADC2-VINB-)") (class "Default")
      (node (ref "ADC2") (pin "7") (pinfunction "VINB-_7") (pintype "input"))
      (node (ref "R28") (pin "2") (pinfunction "2_2") (pintype "passive"))
    )
    (net (code "35") (name "Net-(ADC3-VINA+)") (class "Default")
      (node (ref "ADC3") (pin "1") (pinfunction "VINA+_1") (pintype "input"))
      (node (ref "R37") (pin "2") (pinfunction "2_2") (pintype "passive"))
    )
    (net (code "36") (name "Net-(ADC3-VINA-)") (class "Default")
      (node (ref "ADC3") (pin "2") (pinfunction "VINA-_2") (pintype "input"))
      (node (ref "R38") (pin "2") (pinfunction "2_2") (pintype "passive"))
    )
    (net (code "37") (name "Net-(ADC3-VINB+)") (class "Default")
      (node (ref "ADC3") (pin "8") (pinfunction "VINB+_8") (pintype "input"))
      (node (ref "R43") (pin "2") (pinfunction "2_2") (pintype "passive"))
    )
    (net (code "38") (name "Net-(ADC3-VINB-)") (class "Default")
      (node (ref "ADC3") (pin "7") (pinfunction "VINB-_7") (pintype "input"))
      (node (ref "R44") (pin "2") (pinfunction "2_2") (pintype "passive"))
    )
    (net (code "39") (name "Net-(ADCOP1-+IN)") (class "Default")
      (node (ref "ADCOP1") (pin "8") (pinfunction "+IN_8") (pintype "input"))
      (node (ref "C1") (pin "1") (pinfunction "1_1") (pintype "passive"))
      (node (ref "R4") (pin "1") (pinfunction "1_1") (pintype "passive"))
      (node (ref "R6") (pin "2") (pinfunction "2_2") (pintype "passive"))
    )
    (net (code "40") (name "Net-(ADCOP1-+OUT)") (class "Default")
      (node (ref "ADCOP1") (pin "4") (pinfunction "+OUT_4") (pintype "output"))
      (node (ref "C2") (pin "2") (pinfunction "2_2") (pintype "passive"))
      (node (ref "R1") (pin "1") (pinfunction "1_1") (pintype "passive"))
      (node (ref "R3") (pin "2") (pinfunction "2_2") (pintype "passive"))
    )
    (net (code "41") (name "Net-(ADCOP1--IN)") (class "Default")
      (node (ref "ADCOP1") (pin "1") (pinfunction "-IN_1") (pintype "input"))
      (node (ref "C2") (pin "1") (pinfunction "1_1") (pintype "passive"))
      (node (ref "R3") (pin "1") (pinfunction "1_1") (pintype "passive"))
      (node (ref "R5") (pin "2") (pinfunction "2_2") (pintype "passive"))
    )
    (net (code "42") (name "Net-(ADCOP1--OUT)") (class "Default")
      (node (ref "ADCOP1") (pin "5") (pinfunction "-OUT_5") (pintype "output"))
      (node (ref "C1") (pin "2") (pinfunction "2_2") (pintype "passive"))
      (node (ref "R2") (pin "1") (pinfunction "1_1") (pintype "passive"))
      (node (ref "R4") (pin "2") (pinfunction "2_2") (pintype "passive"))
    )
    (net (code "43") (name "Net-(ADCOP1-VOCM)") (class "Default")
      (node (ref "ADCOP1") (pin "2") (pinfunction "VOCM_2") (pintype "passive"))
      (node (ref "C6") (pin "2") (pinfunction "2_2") (pintype "passive"))
      (node (ref "R16") (pin "2") (pinfunction "2_2") (pintype "passive"))
      (node (ref "R8") (pin "2") (pinfunction "2_2") (pintype "passive"))
    )
    (net (code "44") (name "Net-(ADCOP2-+IN)") (class "Default")
      (node (ref "ADCOP2") (pin "8") (pinfunction "+IN_8") (pintype "input"))
      (node (ref "C4") (pin "1") (pinfunction "1_1") (pintype "passive"))
      (node (ref "R13") (pin "1") (pinfunction "1_1") (pintype "passive"))
      (node (ref "R15") (pin "2") (pinfunction "2_2") (pintype "passive"))
    )
    (net (code "45") (name "Net-(ADCOP2-+OUT)") (class "Default")
      (node (ref "ADCOP2") (pin "4") (pinfunction "+OUT_4") (pintype "output"))
      (node (ref "C5") (pin "2") (pinfunction "2_2") (pintype "passive"))
      (node (ref "R10") (pin "1") (pinfunction "1_1") (pintype "passive"))
      (node (ref "R12") (pin "2") (pinfunction "2_2") (pintype "passive"))
    )
    (net (code "46") (name "Net-(ADCOP2--IN)") (class "Default")
      (node (ref "ADCOP2") (pin "1") (pinfunction "-IN_1") (pintype "input"))
      (node (ref "C5") (pin "1") (pinfunction "1_1") (pintype "passive"))
      (node (ref "R12") (pin "1") (pinfunction "1_1") (pintype "passive"))
      (node (ref "R14") (pin "2") (pinfunction "2_2") (pintype "passive"))
    )
    (net (code "47") (name "Net-(ADCOP2--OUT)") (class "Default")
      (node (ref "ADCOP2") (pin "5") (pinfunction "-OUT_5") (pintype "output"))
      (node (ref "C4") (pin "2") (pinfunction "2_2") (pintype "passive"))
      (node (ref "R11") (pin "1") (pinfunction "1_1") (pintype "passive"))
      (node (ref "R13") (pin "2") (pinfunction "2_2") (pintype "passive"))
    )
    (net (code "48") (name "Net-(ADCOP2-VOCM)") (class "Default")
      (node (ref "ADCOP2") (pin "2") (pinfunction "VOCM_2") (pintype "passive"))
      (node (ref "C3") (pin "1") (pinfunction "1_1") (pintype "passive"))
      (node (ref "R7") (pin "2") (pinfunction "2_2") (pintype "passive"))
      (node (ref "R9") (pin "1") (pinfunction "1_1") (pintype "passive"))
    )
    (net (code "49") (name "Net-(ADCOP3-+IN)") (class "Default")
      (node (ref "ADCOP3") (pin "8") (pinfunction "+IN_8") (pintype "input"))
      (node (ref "C46") (pin "1") (pinfunction "1_1") (pintype "passive"))
      (node (ref "R24") (pin "1") (pinfunction "1_1") (pintype "passive"))
      (node (ref "R26") (pin "2") (pinfunction "2_2") (pintype "passive"))
    )
    (net (code "50") (name "Net-(ADCOP3-+OUT)") (class "Default")
      (node (ref "ADCOP3") (pin "4") (pinfunction "+OUT_4") (pintype "output"))
      (node (ref "C47") (pin "2") (pinfunction "2_2") (pintype "passive"))
      (node (ref "R21") (pin "1") (pinfunction "1_1") (pintype "passive"))
      (node (ref "R23") (pin "2") (pinfunction "2_2") (pintype "passive"))
    )
    (net (code "51") (name "Net-(ADCOP3--IN)") (class "Default")
      (node (ref "ADCOP3") (pin "1") (pinfunction "-IN_1") (pintype "input"))
      (node (ref "C47") (pin "1") (pinfunction "1_1") (pintype "passive"))
      (node (ref "R23") (pin "1") (pinfunction "1_1") (pintype "passive"))
      (node (ref "R25") (pin "2") (pinfunction "2_2") (pintype "passive"))
    )
    (net (code "52") (name "Net-(ADCOP3--OUT)") (class "Default")
      (node (ref "ADCOP3") (pin "5") (pinfunction "-OUT_5") (pintype "output"))
      (node (ref "C46") (pin "2") (pinfunction "2_2") (pintype "passive"))
      (node (ref "R22") (pin "1") (pinfunction "1_1") (pintype "passive"))
      (node (ref "R24") (pin "2") (pinfunction "2_2") (pintype "passive"))
    )
    (net (code "53") (name "Net-(ADCOP3-VOCM)") (class "Default")
      (node (ref "ADCOP3") (pin "2") (pinfunction "VOCM_2") (pintype "passive"))
      (node (ref "C57") (pin "2") (pinfunction "2_2") (pintype "passive"))
      (node (ref "R34") (pin "2") (pinfunction "2_2") (pintype "passive"))
      (node (ref "R36") (pin "2") (pinfunction "2_2") (pintype "passive"))
    )
    (net (code "54") (name "Net-(ADCOP4-+IN)") (class "Default")
      (node (ref "ADCOP4") (pin "8") (pinfunction "+IN_8") (pintype "input"))
      (node (ref "C48") (pin "1") (pinfunction "1_1") (pintype "passive"))
      (node (ref "R30") (pin "1") (pinfunction "1_1") (pintype "passive"))
      (node (ref "R32") (pin "2") (pinfunction "2_2") (pintype "passive"))
    )
    (net (code "55") (name "Net-(ADCOP4-+OUT)") (class "Default")
      (node (ref "ADCOP4") (pin "4") (pinfunction "+OUT_4") (pintype "output"))
      (node (ref "C49") (pin "2") (pinfunction "2_2") (pintype "passive"))
      (node (ref "R27") (pin "1") (pinfunction "1_1") (pintype "passive"))
      (node (ref "R29") (pin "2") (pinfunction "2_2") (pintype "passive"))
    )
    (net (code "56") (name "Net-(ADCOP4--IN)") (class "Default")
      (node (ref "ADCOP4") (pin "1") (pinfunction "-IN_1") (pintype "input"))
      (node (ref "C49") (pin "1") (pinfunction "1_1") (pintype "passive"))
      (node (ref "R29") (pin "1") (pinfunction "1_1") (pintype "passive"))
      (node (ref "R31") (pin "2") (pinfunction "2_2") (pintype "passive"))
    )
    (net (code "57") (name "Net-(ADCOP4--OUT)") (class "Default")
      (node (ref "ADCOP4") (pin "5") (pinfunction "-OUT_5") (pintype "output"))
      (node (ref "C48") (pin "2") (pinfunction "2_2") (pintype "passive"))
      (node (ref "R28") (pin "1") (pinfunction "1_1") (pintype "passive"))
      (node (ref "R30") (pin "2") (pinfunction "2_2") (pintype "passive"))
    )
    (net (code "58") (name "Net-(ADCOP4-VOCM)") (class "Default")
      (node (ref "ADCOP4") (pin "2") (pinfunction "VOCM_2") (pintype "passive"))
      (node (ref "C56") (pin "1") (pinfunction "1_1") (pintype "passive"))
      (node (ref "R33") (pin "2") (pinfunction "2_2") (pintype "passive"))
      (node (ref "R35") (pin "1") (pinfunction "1_1") (pintype "passive"))
    )
    (net (code "59") (name "Net-(ADCOP5-+IN)") (class "Default")
      (node (ref "ADCOP5") (pin "8") (pinfunction "+IN_8") (pintype "input"))
      (node (ref "C74") (pin "1") (pinfunction "1_1") (pintype "passive"))
      (node (ref "R40") (pin "1") (pinfunction "1_1") (pintype "passive"))
      (node (ref "R42") (pin "2") (pinfunction "2_2") (pintype "passive"))
    )
    (net (code "60") (name "Net-(ADCOP5-+OUT)") (class "Default")
      (node (ref "ADCOP5") (pin "4") (pinfunction "+OUT_4") (pintype "output"))
      (node (ref "C75") (pin "2") (pinfunction "2_2") (pintype "passive"))
      (node (ref "R37") (pin "1") (pinfunction "1_1") (pintype "passive"))
      (node (ref "R39") (pin "2") (pinfunction "2_2") (pintype "passive"))
    )
    (net (code "61") (name "Net-(ADCOP5--IN)") (class "Default")
      (node (ref "ADCOP5") (pin "1") (pinfunction "-IN_1") (pintype "input"))
      (node (ref "C75") (pin "1") (pinfunction "1_1") (pintype "passive"))
      (node (ref "R39") (pin "1") (pinfunction "1_1") (pintype "passive"))
      (node (ref "R41") (pin "2") (pinfunction "2_2") (pintype "passive"))
    )
    (net (code "62") (name "Net-(ADCOP5--OUT)") (class "Default")
      (node (ref "ADCOP5") (pin "5") (pinfunction "-OUT_5") (pintype "output"))
      (node (ref "C74") (pin "2") (pinfunction "2_2") (pintype "passive"))
      (node (ref "R38") (pin "1") (pinfunction "1_1") (pintype "passive"))
      (node (ref "R40") (pin "2") (pinfunction "2_2") (pintype "passive"))
    )
    (net (code "63") (name "Net-(ADCOP5-VOCM)") (class "Default")
      (node (ref "ADCOP5") (pin "2") (pinfunction "VOCM_2") (pintype "passive"))
      (node (ref "C85") (pin "2") (pinfunction "2_2") (pintype "passive"))
      (node (ref "R50") (pin "2") (pinfunction "2_2") (pintype "passive"))
      (node (ref "R52") (pin "2") (pinfunction "2_2") (pintype "passive"))
    )
    (net (code "64") (name "Net-(ADCOP6-+IN)") (class "Default")
      (node (ref "ADCOP6") (pin "8") (pinfunction "+IN_8") (pintype "input"))
      (node (ref "C76") (pin "1") (pinfunction "1_1") (pintype "passive"))
      (node (ref "R46") (pin "1") (pinfunction "1_1") (pintype "passive"))
      (node (ref "R48") (pin "2") (pinfunction "2_2") (pintype "passive"))
    )
    (net (code "65") (name "Net-(ADCOP6-+OUT)") (class "Default")
      (node (ref "ADCOP6") (pin "4") (pinfunction "+OUT_4") (pintype "output"))
      (node (ref "C77") (pin "2") (pinfunction "2_2") (pintype "passive"))
      (node (ref "R43") (pin "1") (pinfunction "1_1") (pintype "passive"))
      (node (ref "R45") (pin "2") (pinfunction "2_2") (pintype "passive"))
    )
    (net (code "66") (name "Net-(ADCOP6--IN)") (class "Default")
      (node (ref "ADCOP6") (pin "1") (pinfunction "-IN_1") (pintype "input"))
      (node (ref "C77") (pin "1") (pinfunction "1_1") (pintype "passive"))
      (node (ref "R45") (pin "1") (pinfunction "1_1") (pintype "passive"))
      (node (ref "R47") (pin "2") (pinfunction "2_2") (pintype "passive"))
    )
    (net (code "67") (name "Net-(ADCOP6--OUT)") (class "Default")
      (node (ref "ADCOP6") (pin "5") (pinfunction "-OUT_5") (pintype "output"))
      (node (ref "C76") (pin "2") (pinfunction "2_2") (pintype "passive"))
      (node (ref "R44") (pin "1") (pinfunction "1_1") (pintype "passive"))
      (node (ref "R46") (pin "2") (pinfunction "2_2") (pintype "passive"))
    )
    (net (code "68") (name "Net-(ADCOP6-VOCM)") (class "Default")
      (node (ref "ADCOP6") (pin "2") (pinfunction "VOCM_2") (pintype "passive"))
      (node (ref "C84") (pin "1") (pinfunction "1_1") (pintype "passive"))
      (node (ref "R49") (pin "2") (pinfunction "2_2") (pintype "passive"))
      (node (ref "R51") (pin "1") (pinfunction "1_1") (pintype "passive"))
    )
    (net (code "69") (name "Net-(C25-Pad2)") (class "Default")
      (node (ref "C25") (pin "2") (pinfunction "2_2") (pintype "passive"))
      (node (ref "L1") (pin "1") (pinfunction "1_1") (pintype "passive"))
      (node (ref "R18") (pin "1") (pinfunction "1_1") (pintype "passive"))
      (node (ref "U$1") (pin "A1") (pinfunction "VOUT+_A1") (pintype "bidirectional"))
      (node (ref "U$1") (pin "A2") (pinfunction "VOUT+_A2") (pintype "bidirectional"))
      (node (ref "U$1") (pin "B1") (pinfunction "VOUT+_B1") (pintype "bidirectional"))
      (node (ref "U$1") (pin "B2") (pinfunction "VOUT+_B2") (pintype "bidirectional"))
    )
    (net (code "70") (name "Net-(C27-Pad1)") (class "Default")
      (node (ref "C27") (pin "1") (pinfunction "1_1") (pintype "passive"))
      (node (ref "L2") (pin "1") (pinfunction "1_1") (pintype "passive"))
      (node (ref "R20") (pin "2") (pinfunction "2_2") (pintype "passive"))
      (node (ref "U$2") (pin "A4") (pinfunction "VOUT-_A4") (pintype "bidirectional"))
      (node (ref "U$2") (pin "A5") (pinfunction "VOUT-_A5") (pintype "bidirectional"))
      (node (ref "U$2") (pin "B4") (pinfunction "VOUT-_B4") (pintype "bidirectional"))
      (node (ref "U$2") (pin "B5") (pinfunction "VOUT-_B5") (pintype "bidirectional"))
    )
    (net (code "71") (name "Net-(R6-Pad1)") (class "Default")
      (node (ref "R6") (pin "1") (pinfunction "1_1") (pintype "passive"))
      (node (ref "X1") (pin "1") (pinfunction "1_1") (pintype "passive"))
    )
    (net (code "72") (name "Net-(R15-Pad1)") (class "Default")
      (node (ref "R15") (pin "1") (pinfunction "1_1") (pintype "passive"))
      (node (ref "X2") (pin "1") (pinfunction "1_1") (pintype "passive"))
    )
    (net (code "73") (name "Net-(R26-Pad1)") (class "Default")
      (node (ref "R26") (pin "1") (pinfunction "1_1") (pintype "passive"))
      (node (ref "X11") (pin "1") (pinfunction "1_1") (pintype "passive"))
    )
    (net (code "74") (name "Net-(R32-Pad1)") (class "Default")
      (node (ref "R32") (pin "1") (pinfunction "1_1") (pintype "passive"))
      (node (ref "X12") (pin "1") (pinfunction "1_1") (pintype "passive"))
    )
    (net (code "75") (name "Net-(R42-Pad1)") (class "Default")
      (node (ref "R42") (pin "1") (pinfunction "1_1") (pintype "passive"))
      (node (ref "X13") (pin "1") (pinfunction "1_1") (pintype "passive"))
    )
    (net (code "76") (name "Net-(R48-Pad1)") (class "Default")
      (node (ref "R48") (pin "1") (pinfunction "1_1") (pintype "passive"))
      (node (ref "X14") (pin "1") (pinfunction "1_1") (pintype "passive"))
    )
    (net (code "77") (name "Net-(U$1-FB)") (class "Default")
      (node (ref "R18") (pin "2") (pinfunction "2_2") (pintype "passive"))
      (node (ref "U$1") (pin "A3") (pinfunction "FB_A3") (pintype "bidirectional"))
    )
    (net (code "78") (name "Net-(U$1-RT)") (class "Default")
      (node (ref "R17") (pin "2") (pinfunction "2_2") (pintype "passive"))
      (node (ref "U$1") (pin "G1") (pinfunction "RT_G1") (pintype "bidirectional"))
    )
    (net (code "79") (name "Net-(U$2-FB)") (class "Default")
      (node (ref "R20") (pin "1") (pinfunction "1_1") (pintype "passive"))
      (node (ref "U$2") (pin "A3") (pinfunction "FB_A3") (pintype "bidirectional"))
    )
    (net (code "80") (name "Net-(U$2-RT)") (class "Default")
      (node (ref "R19") (pin "2") (pinfunction "2_2") (pintype "passive"))
      (node (ref "U$2") (pin "G1") (pinfunction "RT_G1") (pintype "bidirectional"))
    )
    (net (code "81") (name "Net-(U$4-1)") (class "Default")
      (node (ref "L1") (pin "2") (pinfunction "2_2") (pintype "passive"))
      (node (ref "U$4") (pin "IN") (pinfunction "1_IN") (pintype "passive"))
    )
    (net (code "82") (name "Net-(U$4-3)") (class "Default")
      (node (ref "U$4") (pin "OUT") (pinfunction "3_OUT") (pintype "passive"))
      (node (ref "U5") (pin "5") (pinfunction "~{SHDN}_5") (pintype "input"))
      (node (ref "U5") (pin "8") (pinfunction "IN_8") (pintype "input"))
    )
    (net (code "83") (name "Net-(U$5-1)") (class "Default")
      (node (ref "L2") (pin "2") (pinfunction "2_2") (pintype "passive"))
      (node (ref "U$5") (pin "IN") (pinfunction "1_IN") (pintype "passive"))
    )
    (net (code "84") (name "Net-(U$5-3)") (class "Default")
      (node (ref "U$5") (pin "OUT") (pinfunction "3_OUT") (pintype "passive"))
      (node (ref "U4") (pin "1") (pinfunction "VIN_2_1") (pintype "input"))
      (node (ref "U4") (pin "2") (pinfunction "ILIM2_2") (pintype "input"))
      (node (ref "U4") (pin "7") (pinfunction "ILIM4_7") (pintype "input"))
      (node (ref "U4") (pin "8") (pinfunction "VIN_8") (pintype "input"))
    )
    (net (code "85") (name "Net-(U$6-1)") (class "Default")
      (node (ref "C98") (pin "-") (pinfunction "-_-") (pintype "passive"))
      (node (ref "U$6") (pin "IN") (pinfunction "1_IN") (pintype "passive"))
      (node (ref "U4") (pin "3") (pinfunction "OUTPUT_3") (pintype "output"))
      (node (ref "U4") (pin "4") (pinfunction "SENSE_4") (pintype "input"))
    )
    (net (code "86") (name "Net-(U$7-1)") (class "Default")
      (node (ref "C29") (pin "+") (pinfunction "+_+") (pintype "passive"))
      (node (ref "C31") (pin "2") (pinfunction "2_2") (pintype "passive"))
      (node (ref "U$7") (pin "IN") (pinfunction "1_IN") (pintype "passive"))
      (node (ref "U5") (pin "1") (pinfunction "OUT_1") (pintype "output"))
      (node (ref "U5") (pin "2") (pinfunction "SENSE_2") (pintype "input"))
    )
    (net (code "87") (name "Net-(U1--IN1)") (class "Default")
      (node (ref "R8") (pin "1") (pinfunction "1_1") (pintype "passive"))
      (node (ref "U1") (pin "1") (pinfunction "OUT1_1") (pintype "output"))
      (node (ref "U1") (pin "2") (pinfunction "-IN1_2") (pintype "input"))
    )
    (net (code "88") (name "Net-(U1--IN2)") (class "Default")
      (node (ref "R7") (pin "1") (pinfunction "1_1") (pintype "passive"))
      (node (ref "U1") (pin "6") (pinfunction "-IN2_6") (pintype "input"))
      (node (ref "U1") (pin "7") (pinfunction "OUT2_7") (pintype "output"))
    )
    (net (code "89") (name "Net-(U2-REFIN)") (class "Default")
      (node (ref "C38") (pin "2") (pinfunction "2_2") (pintype "passive"))
      (node (ref "U2") (pin "17") (pinfunction "REFIN_17") (pintype "passive"))
      (node (ref "U3") (pin "6") (pinfunction "VOUT_6") (pintype "output"))
    )
    (net (code "90") (name "Net-(U2-VOUTA)") (class "Default")
      (node (ref "U2") (pin "3") (pinfunction "VOUTA_3") (pintype "passive"))
      (node (ref "X8") (pin "1") (pinfunction "1_1") (pintype "passive"))
    )
    (net (code "91") (name "Net-(U2-VOUTB)") (class "Default")
      (node (ref "U2") (pin "4") (pinfunction "VOUTB_4") (pintype "passive"))
      (node (ref "X7") (pin "1") (pinfunction "1_1") (pintype "passive"))
    )
    (net (code "92") (name "Net-(U2-VOUTC)") (class "Default")
      (node (ref "U2") (pin "23") (pinfunction "VOUTC_23") (pintype "passive"))
      (node (ref "X6") (pin "1") (pinfunction "1_1") (pintype "passive"))
    )
    (net (code "93") (name "Net-(U2-VOUTD)") (class "Default")
      (node (ref "U2") (pin "22") (pinfunction "VOUTD_22") (pintype "passive"))
      (node (ref "X5") (pin "1") (pinfunction "1_1") (pintype "passive"))
    )
    (net (code "94") (name "Net-(U5-BYP)") (class "Default")
      (node (ref "C31") (pin "1") (pinfunction "1_1") (pintype "passive"))
      (node (ref "U5") (pin "4") (pinfunction "BYP_4") (pintype "passive"))
    )
    (net (code "95") (name "Net-(U6-REFIN)") (class "Default")
      (node (ref "C37") (pin "2") (pinfunction "2_2") (pintype "passive"))
      (node (ref "U6") (pin "17") (pinfunction "REFIN_17") (pintype "passive"))
      (node (ref "U7") (pin "6") (pinfunction "VOUT_6") (pintype "output"))
    )
    (net (code "96") (name "Net-(U6-VOUTA)") (class "Default")
      (node (ref "U6") (pin "3") (pinfunction "VOUTA_3") (pintype "passive"))
      (node (ref "X10") (pin "1") (pinfunction "1_1") (pintype "passive"))
    )
    (net (code "97") (name "Net-(U6-VOUTB)") (class "Default")
      (node (ref "U6") (pin "4") (pinfunction "VOUTB_4") (pintype "passive"))
      (node (ref "X9") (pin "1") (pinfunction "1_1") (pintype "passive"))
    )
    (net (code "98") (name "Net-(U6-VOUTC)") (class "Default")
      (node (ref "U6") (pin "23") (pinfunction "VOUTC_23") (pintype "passive"))
      (node (ref "X4") (pin "1") (pinfunction "1_1") (pintype "passive"))
    )
    (net (code "99") (name "Net-(U6-VOUTD)") (class "Default")
      (node (ref "U6") (pin "22") (pinfunction "VOUTD_22") (pintype "passive"))
      (node (ref "X3") (pin "1") (pinfunction "1_1") (pintype "passive"))
    )
    (net (code "100") (name "Net-(U8--IN1)") (class "Default")
      (node (ref "R34") (pin "1") (pinfunction "1_1") (pintype "passive"))
      (node (ref "U8") (pin "1") (pinfunction "OUT1_1") (pintype "output"))
      (node (ref "U8") (pin "2") (pinfunction "-IN1_2") (pintype "input"))
    )
    (net (code "101") (name "Net-(U8--IN2)") (class "Default")
      (node (ref "R33") (pin "1") (pinfunction "1_1") (pintype "passive"))
      (node (ref "U8") (pin "6") (pinfunction "-IN2_6") (pintype "input"))
      (node (ref "U8") (pin "7") (pinfunction "OUT2_7") (pintype "output"))
    )
    (net (code "102") (name "Net-(U9--IN1)") (class "Default")
      (node (ref "R50") (pin "1") (pinfunction "1_1") (pintype "passive"))
      (node (ref "U9") (pin "1") (pinfunction "OUT1_1") (pintype "output"))
      (node (ref "U9") (pin "2") (pinfunction "-IN1_2") (pintype "input"))
    )
    (net (code "103") (name "Net-(U9--IN2)") (class "Default")
      (node (ref "R49") (pin "1") (pinfunction "1_1") (pintype "passive"))
      (node (ref "U9") (pin "6") (pinfunction "-IN2_6") (pintype "input"))
      (node (ref "U9") (pin "7") (pinfunction "OUT2_7") (pintype "output"))
    )
    (net (code "104") (name "V+") (class "Default")
      (node (ref "C26") (pin "1") (pinfunction "1_1") (pintype "passive"))
      (node (ref "C28") (pin "1") (pinfunction "1_1") (pintype "passive"))
      (node (ref "C35") (pin "+") (pinfunction "+_+") (pintype "passive"))
      (node (ref "C36") (pin "+") (pinfunction "+_+") (pintype "passive"))
      (node (ref "J1") (pin "101") (pinfunction "P$101_101") (pintype "bidirectional"))
      (node (ref "J1") (pin "103") (pinfunction "P$103_103") (pintype "bidirectional"))
      (node (ref "J1") (pin "105") (pinfunction "P$105_105") (pintype "bidirectional"))
      (node (ref "U$1") (pin "G3") (pinfunction "RUN_G3") (pintype "bidirectional"))
      (node (ref "U$1") (pin "G4") (pinfunction "V_IN_G4") (pintype "bidirectional"))
      (node (ref "U$1") (pin "G5") (pinfunction "V_IN_G5") (pintype "bidirectional"))
      (node (ref "U$1") (pin "H4") (pinfunction "V_IN_H4") (pintype "bidirectional"))
      (node (ref "U$1") (pin "H5") (pinfunction "V_IN_H5") (pintype "bidirectional"))
      (node (ref "U$2") (pin "G3") (pinfunction "RUN_G3") (pintype "bidirectional"))
      (node (ref "U$2") (pin "G4") (pinfunction "V_IN_G4") (pintype "bidirectional"))
      (node (ref "U$2") (pin "G5") (pinfunction "V_IN_G5") (pintype "bidirectional"))
      (node (ref "U$2") (pin "H4") (pinfunction "V_IN_H4") (pintype "bidirectional"))
      (node (ref "U$2") (pin "H5") (pinfunction "V_IN_H5") (pintype "bidirectional"))
    )
    (net (code "105") (name "VDD") (class "Default")
      (node (ref "ADC1") (pin "9") (pinfunction "VDD_9") (pintype "power_in"))
      (node (ref "ADC2") (pin "9") (pinfunction "VDD_9") (pintype "power_in"))
      (node (ref "ADC3") (pin "9") (pinfunction "VDD_9") (pintype "power_in"))
      (node (ref "C100") (pin "1") (pinfunction "1_1") (pintype "passive"))
      (node (ref "C11") (pin "1") (pinfunction "1_1") (pintype "passive"))
      (node (ref "C50") (pin "+") (pinfunction "+_+") (pintype "passive"))
      (node (ref "C53") (pin "1") (pinfunction "1_1") (pintype "passive"))
      (node (ref "C78") (pin "+") (pinfunction "+_+") (pintype "passive"))
      (node (ref "C8") (pin "+") (pinfunction "+_+") (pintype "passive"))
      (node (ref "C81") (pin "1") (pinfunction "1_1") (pintype "passive"))
      (node (ref "U$3") (pin "4") (pinfunction "SENSE2_4") (pintype "passive"))
      (node (ref "U$3") (pin "5") (pinfunction "VOUT2_5") (pintype "passive"))
    )
    (net (code "106") (name "VREF1A") (class "Default")
      (node (ref "ADC1") (pin "3") (pinfunction "REFA_3") (pintype "input"))
      (node (ref "C12") (pin "+") (pinfunction "+_+") (pintype "passive"))
      (node (ref "U1") (pin "3") (pinfunction "+IN1_3") (pintype "input"))
    )
    (net (code "107") (name "VREF1B") (class "Default")
      (node (ref "ADC1") (pin "6") (pinfunction "REFB_6") (pintype "input"))
      (node (ref "C13") (pin "+") (pinfunction "+_+") (pintype "passive"))
      (node (ref "U1") (pin "5") (pinfunction "+IN2_5") (pintype "input"))
    )
    (net (code "108") (name "VREF2A") (class "Default")
      (node (ref "ADC2") (pin "3") (pinfunction "REFA_3") (pintype "input"))
      (node (ref "C54") (pin "+") (pinfunction "+_+") (pintype "passive"))
      (node (ref "U8") (pin "3") (pinfunction "+IN1_3") (pintype "input"))
    )
    (net (code "109") (name "VREF2B") (class "Default")
      (node (ref "ADC2") (pin "6") (pinfunction "REFB_6") (pintype "input"))
      (node (ref "C55") (pin "+") (pinfunction "+_+") (pintype "passive"))
      (node (ref "U8") (pin "5") (pinfunction "+IN2_5") (pintype "input"))
    )
    (net (code "110") (name "VREF3A") (class "Default")
      (node (ref "ADC3") (pin "3") (pinfunction "REFA_3") (pintype "input"))
      (node (ref "C82") (pin "+") (pinfunction "+_+") (pintype "passive"))
      (node (ref "U9") (pin "3") (pinfunction "+IN1_3") (pintype "input"))
    )
    (net (code "111") (name "VREF3B") (class "Default")
      (node (ref "ADC3") (pin "6") (pinfunction "REFB_6") (pintype "input"))
      (node (ref "C83") (pin "+") (pinfunction "+_+") (pintype "passive"))
      (node (ref "U9") (pin "5") (pinfunction "+IN2_5") (pintype "input"))
    )
    (net (code "112") (name "unconnected-(ADCOP1-NC-Pad7)") (class "Default")
      (node (ref "ADCOP1") (pin "7") (pinfunction "NC_7") (pintype "no_connect"))
    )
    (net (code "113") (name "unconnected-(ADCOP2-NC-Pad7)") (class "Default")
      (node (ref "ADCOP2") (pin "7") (pinfunction "NC_7") (pintype "no_connect"))
    )
    (net (code "114") (name "unconnected-(ADCOP3-NC-Pad7)") (class "Default")
      (node (ref "ADCOP3") (pin "7") (pinfunction "NC_7") (pintype "no_connect"))
    )
    (net (code "115") (name "unconnected-(ADCOP4-NC-Pad7)") (class "Default")
      (node (ref "ADCOP4") (pin "7") (pinfunction "NC_7") (pintype "no_connect"))
    )
    (net (code "116") (name "unconnected-(ADCOP5-NC-Pad7)") (class "Default")
      (node (ref "ADCOP5") (pin "7") (pinfunction "NC_7") (pintype "no_connect"))
    )
    (net (code "117") (name "unconnected-(ADCOP6-NC-Pad7)") (class "Default")
      (node (ref "ADCOP6") (pin "7") (pinfunction "NC_7") (pintype "no_connect"))
    )
    (net (code "118") (name "unconnected-(J1-P$2-Pad202)") (class "Default")
      (node (ref "J1") (pin "202") (pinfunction "P$2_202") (pintype "bidirectional"))
    )
    (net (code "119") (name "unconnected-(J1-P$3-Pad203)") (class "Default")
      (node (ref "J1") (pin "203") (pinfunction "P$3_203") (pintype "bidirectional"))
    )
    (net (code "120") (name "unconnected-(J1-P$4-Pad204)") (class "Default")
      (node (ref "J1") (pin "204") (pinfunction "P$4_204") (pintype "bidirectional"))
    )
    (net (code "121") (name "unconnected-(J1-P$5-Pad205)") (class "Default")
      (node (ref "J1") (pin "205") (pinfunction "P$5_205") (pintype "bidirectional"))
    )
    (net (code "122") (name "unconnected-(J1-P$6-Pad206)") (class "Default")
      (node (ref "J1") (pin "206") (pinfunction "P$6_206") (pintype "bidirectional"))
    )
    (net (code "123") (name "unconnected-(J1-P$7-Pad207)") (class "Default")
      (node (ref "J1") (pin "207") (pinfunction "P$7_207") (pintype "bidirectional"))
    )
    (net (code "124") (name "unconnected-(J1-P$8-Pad208)") (class "Default")
      (node (ref "J1") (pin "208") (pinfunction "P$8_208") (pintype "bidirectional"))
    )
    (net (code "125") (name "unconnected-(J1-P$9-Pad209)") (class "Default")
      (node (ref "J1") (pin "209") (pinfunction "P$9_209") (pintype "bidirectional"))
    )
    (net (code "126") (name "unconnected-(J1-P$10-Pad210)") (class "Default")
      (node (ref "J1") (pin "210") (pinfunction "P$10_210") (pintype "bidirectional"))
    )
    (net (code "127") (name "unconnected-(J1-P$11-Pad211)") (class "Default")
      (node (ref "J1") (pin "211") (pinfunction "P$11_211") (pintype "bidirectional"))
    )
    (net (code "128") (name "unconnected-(J1-P$12-Pad212)") (class "Default")
      (node (ref "J1") (pin "212") (pinfunction "P$12_212") (pintype "bidirectional"))
    )
    (net (code "129") (name "unconnected-(J1-P$23-Pad223)") (class "Default")
      (node (ref "J1") (pin "223") (pinfunction "P$23_223") (pintype "bidirectional"))
    )
    (net (code "130") (name "unconnected-(J1-P$24-Pad224)") (class "Default")
      (node (ref "J1") (pin "224") (pinfunction "P$24_224") (pintype "bidirectional"))
    )
    (net (code "131") (name "unconnected-(J1-P$25-Pad225)") (class "Default")
      (node (ref "J1") (pin "225") (pinfunction "P$25_225") (pintype "bidirectional"))
    )
    (net (code "132") (name "unconnected-(J1-P$26-Pad226)") (class "Default")
      (node (ref "J1") (pin "226") (pinfunction "P$26_226") (pintype "bidirectional"))
    )
    (net (code "133") (name "unconnected-(J1-P$27-Pad227)") (class "Default")
      (node (ref "J1") (pin "227") (pinfunction "P$27_227") (pintype "bidirectional"))
    )
    (net (code "134") (name "unconnected-(J1-P$28-Pad228)") (class "Default")
      (node (ref "J1") (pin "228") (pinfunction "P$28_228") (pintype "bidirectional"))
    )
    (net (code "135") (name "unconnected-(J1-P$29-Pad229)") (class "Default")
      (node (ref "J1") (pin "229") (pinfunction "P$29_229") (pintype "bidirectional"))
    )
    (net (code "136") (name "unconnected-(J1-P$30-Pad230)") (class "Default")
      (node (ref "J1") (pin "230") (pinfunction "P$30_230") (pintype "bidirectional"))
    )
    (net (code "137") (name "unconnected-(J1-P$31-Pad231)") (class "Default")
      (node (ref "J1") (pin "231") (pinfunction "P$31_231") (pintype "bidirectional"))
    )
    (net (code "138") (name "unconnected-(J1-P$32-Pad232)") (class "Default")
      (node (ref "J1") (pin "232") (pinfunction "P$32_232") (pintype "bidirectional"))
    )
    (net (code "139") (name "unconnected-(J1-P$33-Pad233)") (class "Default")
      (node (ref "J1") (pin "233") (pinfunction "P$33_233") (pintype "bidirectional"))
    )
    (net (code "140") (name "unconnected-(J1-P$34-Pad234)") (class "Default")
      (node (ref "J1") (pin "234") (pinfunction "P$34_234") (pintype "bidirectional"))
    )
    (net (code "141") (name "unconnected-(J1-P$35-Pad235)") (class "Default")
      (node (ref "J1") (pin "235") (pinfunction "P$35_235") (pintype "bidirectional"))
    )
    (net (code "142") (name "unconnected-(J1-P$37-Pad237)") (class "Default")
      (node (ref "J1") (pin "237") (pinfunction "P$37_237") (pintype "bidirectional"))
    )
    (net (code "143") (name "unconnected-(J1-P$38-Pad238)") (class "Default")
      (node (ref "J1") (pin "238") (pinfunction "P$38_238") (pintype "bidirectional"))
    )
    (net (code "144") (name "unconnected-(J1-P$39-Pad239)") (class "Default")
      (node (ref "J1") (pin "239") (pinfunction "P$39_239") (pintype "bidirectional"))
    )
    (net (code "145") (name "unconnected-(J1-P$40-Pad240)") (class "Default")
      (node (ref "J1") (pin "240") (pinfunction "P$40_240") (pintype "bidirectional"))
    )
    (net (code "146") (name "unconnected-(J1-P$41-Pad241)") (class "Default")
      (node (ref "J1") (pin "241") (pinfunction "P$41_241") (pintype "bidirectional"))
    )
    (net (code "147") (name "unconnected-(J1-P$42-Pad242)") (class "Default")
      (node (ref "J1") (pin "242") (pinfunction "P$42_242") (pintype "bidirectional"))
    )
    (net (code "148") (name "unconnected-(J1-P$43-Pad243)") (class "Default")
      (node (ref "J1") (pin "243") (pinfunction "P$43_243") (pintype "bidirectional"))
    )
    (net (code "149") (name "unconnected-(J1-P$44-Pad244)") (class "Default")
      (node (ref "J1") (pin "244") (pinfunction "P$44_244") (pintype "bidirectional"))
    )
    (net (code "150") (name "unconnected-(J1-P$45-Pad245)") (class "Default")
      (node (ref "J1") (pin "245") (pinfunction "P$45_245") (pintype "bidirectional"))
    )
    (net (code "151") (name "unconnected-(J1-P$46-Pad246)") (class "Default")
      (node (ref "J1") (pin "246") (pinfunction "P$46_246") (pintype "bidirectional"))
    )
    (net (code "152") (name "unconnected-(J1-P$47-Pad247)") (class "Default")
      (node (ref "J1") (pin "247") (pinfunction "P$47_247") (pintype "bidirectional"))
    )
    (net (code "153") (name "unconnected-(J1-P$48-Pad248)") (class "Default")
      (node (ref "J1") (pin "248") (pinfunction "P$48_248") (pintype "bidirectional"))
    )
    (net (code "154") (name "unconnected-(J1-P$49-Pad249)") (class "Default")
      (node (ref "J1") (pin "249") (pinfunction "P$49_249") (pintype "bidirectional"))
    )
    (net (code "155") (name "unconnected-(J1-P$50-Pad250)") (class "Default")
      (node (ref "J1") (pin "250") (pinfunction "P$50_250") (pintype "bidirectional"))
    )
    (net (code "156") (name "unconnected-(J1-P$51-Pad251)") (class "Default")
      (node (ref "J1") (pin "251") (pinfunction "P$51_251") (pintype "bidirectional"))
    )
    (net (code "157") (name "unconnected-(J1-P$52-Pad252)") (class "Default")
      (node (ref "J1") (pin "252") (pinfunction "P$52_252") (pintype "bidirectional"))
    )
    (net (code "158") (name "unconnected-(J1-P$53-Pad253)") (class "Default")
      (node (ref "J1") (pin "253") (pinfunction "P$53_253") (pintype "bidirectional"))
    )
    (net (code "159") (name "unconnected-(J1-P$54-Pad254)") (class "Default")
      (node (ref "J1") (pin "254") (pinfunction "P$54_254") (pintype "bidirectional"))
    )
    (net (code "160") (name "unconnected-(J1-P$55-Pad255)") (class "Default")
      (node (ref "J1") (pin "255") (pinfunction "P$55_255") (pintype "bidirectional"))
    )
    (net (code "161") (name "unconnected-(J1-P$57-Pad257)") (class "Default")
      (node (ref "J1") (pin "257") (pinfunction "P$57_257") (pintype "bidirectional"))
    )
    (net (code "162") (name "unconnected-(J1-P$58-Pad258)") (class "Default")
      (node (ref "J1") (pin "258") (pinfunction "P$58_258") (pintype "bidirectional"))
    )
    (net (code "163") (name "unconnected-(J1-P$59-Pad259)") (class "Default")
      (node (ref "J1") (pin "259") (pinfunction "P$59_259") (pintype "bidirectional"))
    )
    (net (code "164") (name "unconnected-(J1-P$61-Pad261)") (class "Default")
      (node (ref "J1") (pin "261") (pinfunction "P$61_261") (pintype "bidirectional"))
    )
    (net (code "165") (name "unconnected-(J1-P$63-Pad263)") (class "Default")
      (node (ref "J1") (pin "263") (pinfunction "P$63_263") (pintype "bidirectional"))
    )
    (net (code "166") (name "unconnected-(J1-P$65-Pad265)") (class "Default")
      (node (ref "J1") (pin "265") (pinfunction "P$65_265") (pintype "bidirectional"))
    )
    (net (code "167") (name "unconnected-(J1-P$77-Pad277)") (class "Default")
      (node (ref "J1") (pin "277") (pinfunction "P$77_277") (pintype "bidirectional"))
    )
    (net (code "168") (name "unconnected-(J1-P$79-Pad279)") (class "Default")
      (node (ref "J1") (pin "279") (pinfunction "P$79_279") (pintype "bidirectional"))
    )
    (net (code "169") (name "unconnected-(J1-P$104-Pad104)") (class "Default")
      (node (ref "J1") (pin "104") (pinfunction "P$104_104") (pintype "bidirectional"))
    )
    (net (code "170") (name "unconnected-(J1-P$106-Pad106)") (class "Default")
      (node (ref "J1") (pin "106") (pinfunction "P$106_106") (pintype "bidirectional"))
    )
    (net (code "171") (name "unconnected-(J1-P$107-Pad107)") (class "Default")
      (node (ref "J1") (pin "107") (pinfunction "P$107_107") (pintype "bidirectional"))
    )
    (net (code "172") (name "unconnected-(J1-P$108-Pad108)") (class "Default")
      (node (ref "J1") (pin "108") (pinfunction "P$108_108") (pintype "bidirectional"))
    )
    (net (code "173") (name "unconnected-(J1-P$109-Pad109)") (class "Default")
      (node (ref "J1") (pin "109") (pinfunction "P$109_109") (pintype "bidirectional"))
    )
    (net (code "174") (name "unconnected-(J1-P$110-Pad110)") (class "Default")
      (node (ref "J1") (pin "110") (pinfunction "P$110_110") (pintype "bidirectional"))
    )
    (net (code "175") (name "unconnected-(J1-P$111-Pad111)") (class "Default")
      (node (ref "J1") (pin "111") (pinfunction "P$111_111") (pintype "bidirectional"))
    )
    (net (code "176") (name "unconnected-(J1-P$112-Pad112)") (class "Default")
      (node (ref "J1") (pin "112") (pinfunction "P$112_112") (pintype "bidirectional"))
    )
    (net (code "177") (name "unconnected-(J1-P$113-Pad113)") (class "Default")
      (node (ref "J1") (pin "113") (pinfunction "P$113_113") (pintype "bidirectional"))
    )
    (net (code "178") (name "unconnected-(J1-P$115-Pad115)") (class "Default")
      (node (ref "J1") (pin "115") (pinfunction "P$115_115") (pintype "bidirectional"))
    )
    (net (code "179") (name "unconnected-(J1-P$116-Pad116)") (class "Default")
      (node (ref "J1") (pin "116") (pinfunction "P$116_116") (pintype "bidirectional"))
    )
    (net (code "180") (name "unconnected-(J1-P$117-Pad117)") (class "Default")
      (node (ref "J1") (pin "117") (pinfunction "P$117_117") (pintype "bidirectional"))
    )
    (net (code "181") (name "unconnected-(J1-P$118-Pad118)") (class "Default")
      (node (ref "J1") (pin "118") (pinfunction "P$118_118") (pintype "bidirectional"))
    )
    (net (code "182") (name "unconnected-(J1-P$119-Pad119)") (class "Default")
      (node (ref "J1") (pin "119") (pinfunction "P$119_119") (pintype "bidirectional"))
    )
    (net (code "183") (name "unconnected-(J1-P$120-Pad120)") (class "Default")
      (node (ref "J1") (pin "120") (pinfunction "P$120_120") (pintype "bidirectional"))
    )
    (net (code "184") (name "unconnected-(J1-P$121-Pad121)") (class "Default")
      (node (ref "J1") (pin "121") (pinfunction "P$121_121") (pintype "bidirectional"))
    )
    (net (code "185") (name "unconnected-(J1-P$122-Pad122)") (class "Default")
      (node (ref "J1") (pin "122") (pinfunction "P$122_122") (pintype "bidirectional"))
    )
    (net (code "186") (name "unconnected-(J1-P$123-Pad123)") (class "Default")
      (node (ref "J1") (pin "123") (pinfunction "P$123_123") (pintype "bidirectional"))
    )
    (net (code "187") (name "unconnected-(J1-P$124-Pad124)") (class "Default")
      (node (ref "J1") (pin "124") (pinfunction "P$124_124") (pintype "bidirectional"))
    )
    (net (code "188") (name "unconnected-(J1-P$125-Pad125)") (class "Default")
      (node (ref "J1") (pin "125") (pinfunction "P$125_125") (pintype "bidirectional"))
    )
    (net (code "189") (name "unconnected-(J1-P$126-Pad126)") (class "Default")
      (node (ref "J1") (pin "126") (pinfunction "P$126_126") (pintype "bidirectional"))
    )
    (net (code "190") (name "unconnected-(J1-P$127-Pad127)") (class "Default")
      (node (ref "J1") (pin "127") (pinfunction "P$127_127") (pintype "bidirectional"))
    )
    (net (code "191") (name "unconnected-(J1-P$128-Pad128)") (class "Default")
      (node (ref "J1") (pin "128") (pinfunction "P$128_128") (pintype "bidirectional"))
    )
    (net (code "192") (name "unconnected-(J1-P$129-Pad129)") (class "Default")
      (node (ref "J1") (pin "129") (pinfunction "P$129_129") (pintype "bidirectional"))
    )
    (net (code "193") (name "unconnected-(J1-P$130-Pad130)") (class "Default")
      (node (ref "J1") (pin "130") (pinfunction "P$130_130") (pintype "bidirectional"))
    )
    (net (code "194") (name "unconnected-(J1-P$131-Pad131)") (class "Default")
      (node (ref "J1") (pin "131") (pinfunction "P$131_131") (pintype "bidirectional"))
    )
    (net (code "195") (name "unconnected-(J1-P$132-Pad132)") (class "Default")
      (node (ref "J1") (pin "132") (pinfunction "P$132_132") (pintype "bidirectional"))
    )
    (net (code "196") (name "unconnected-(J1-P$133-Pad133)") (class "Default")
      (node (ref "J1") (pin "133") (pinfunction "P$133_133") (pintype "bidirectional"))
    )
    (net (code "197") (name "unconnected-(J1-P$134-Pad134)") (class "Default")
      (node (ref "J1") (pin "134") (pinfunction "P$134_134") (pintype "bidirectional"))
    )
    (net (code "198") (name "unconnected-(J1-P$136-Pad136)") (class "Default")
      (node (ref "J1") (pin "136") (pinfunction "P$136_136") (pintype "bidirectional"))
    )
    (net (code "199") (name "unconnected-(J1-P$137-Pad137)") (class "Default")
      (node (ref "J1") (pin "137") (pinfunction "P$137_137") (pintype "bidirectional"))
    )
    (net (code "200") (name "unconnected-(J1-P$138-Pad138)") (class "Default")
      (node (ref "J1") (pin "138") (pinfunction "P$138_138") (pintype "bidirectional"))
    )
    (net (code "201") (name "unconnected-(J1-P$139-Pad139)") (class "Default")
      (node (ref "J1") (pin "139") (pinfunction "P$139_139") (pintype "bidirectional"))
    )
    (net (code "202") (name "unconnected-(J1-P$140-Pad140)") (class "Default")
      (node (ref "J1") (pin "140") (pinfunction "P$140_140") (pintype "bidirectional"))
    )
    (net (code "203") (name "unconnected-(J1-P$141-Pad141)") (class "Default")
      (node (ref "J1") (pin "141") (pinfunction "P$141_141") (pintype "bidirectional"))
    )
    (net (code "204") (name "unconnected-(J1-P$142-Pad142)") (class "Default")
      (node (ref "J1") (pin "142") (pinfunction "P$142_142") (pintype "bidirectional"))
    )
    (net (code "205") (name "unconnected-(J1-P$143-Pad143)") (class "Default")
      (node (ref "J1") (pin "143") (pinfunction "P$143_143") (pintype "bidirectional"))
    )
    (net (code "206") (name "unconnected-(J1-P$144-Pad144)") (class "Default")
      (node (ref "J1") (pin "144") (pinfunction "P$144_144") (pintype "bidirectional"))
    )
    (net (code "207") (name "unconnected-(J1-P$145-Pad145)") (class "Default")
      (node (ref "J1") (pin "145") (pinfunction "P$145_145") (pintype "bidirectional"))
    )
    (net (code "208") (name "unconnected-(J1-P$146-Pad146)") (class "Default")
      (node (ref "J1") (pin "146") (pinfunction "P$146_146") (pintype "bidirectional"))
    )
    (net (code "209") (name "unconnected-(J1-P$147-Pad147)") (class "Default")
      (node (ref "J1") (pin "147") (pinfunction "P$147_147") (pintype "bidirectional"))
    )
    (net (code "210") (name "unconnected-(J1-P$148-Pad148)") (class "Default")
      (node (ref "J1") (pin "148") (pinfunction "P$148_148") (pintype "bidirectional"))
    )
    (net (code "211") (name "unconnected-(J1-P$149-Pad149)") (class "Default")
      (node (ref "J1") (pin "149") (pinfunction "P$149_149") (pintype "bidirectional"))
    )
    (net (code "212") (name "unconnected-(J1-P$150-Pad150)") (class "Default")
      (node (ref "J1") (pin "150") (pinfunction "P$150_150") (pintype "bidirectional"))
    )
    (net (code "213") (name "unconnected-(J1-P$151-Pad151)") (class "Default")
      (node (ref "J1") (pin "151") (pinfunction "P$151_151") (pintype "bidirectional"))
    )
    (net (code "214") (name "unconnected-(J1-P$152-Pad152)") (class "Default")
      (node (ref "J1") (pin "152") (pinfunction "P$152_152") (pintype "bidirectional"))
    )
    (net (code "215") (name "unconnected-(J1-P$153-Pad153)") (class "Default")
      (node (ref "J1") (pin "153") (pinfunction "P$153_153") (pintype "bidirectional"))
    )
    (net (code "216") (name "unconnected-(J1-P$154-Pad154)") (class "Default")
      (node (ref "J1") (pin "154") (pinfunction "P$154_154") (pintype "bidirectional"))
    )
    (net (code "217") (name "unconnected-(J1-P$156-Pad156)") (class "Default")
      (node (ref "J1") (pin "156") (pinfunction "P$156_156") (pintype "bidirectional"))
    )
    (net (code "218") (name "unconnected-(J1-P$157-Pad157)") (class "Default")
      (node (ref "J1") (pin "157") (pinfunction "P$157_157") (pintype "bidirectional"))
    )
    (net (code "219") (name "unconnected-(J1-P$158-Pad158)") (class "Default")
      (node (ref "J1") (pin "158") (pinfunction "P$158_158") (pintype "bidirectional"))
    )
    (net (code "220") (name "unconnected-(J1-P$159-Pad159)") (class "Default")
      (node (ref "J1") (pin "159") (pinfunction "P$159_159") (pintype "bidirectional"))
    )
    (net (code "221") (name "unconnected-(J1-P$160-Pad160)") (class "Default")
      (node (ref "J1") (pin "160") (pinfunction "P$160_160") (pintype "bidirectional"))
    )
    (net (code "222") (name "unconnected-(J1-P$161-Pad161)") (class "Default")
      (node (ref "J1") (pin "161") (pinfunction "P$161_161") (pintype "bidirectional"))
    )
    (net (code "223") (name "unconnected-(J1-P$162-Pad162)") (class "Default")
      (node (ref "J1") (pin "162") (pinfunction "P$162_162") (pintype "bidirectional"))
    )
    (net (code "224") (name "unconnected-(J1-P$163-Pad163)") (class "Default")
      (node (ref "J1") (pin "163") (pinfunction "P$163_163") (pintype "bidirectional"))
    )
    (net (code "225") (name "unconnected-(J1-P$164-Pad164)") (class "Default")
      (node (ref "J1") (pin "164") (pinfunction "P$164_164") (pintype "bidirectional"))
    )
    (net (code "226") (name "unconnected-(J1-P$165-Pad165)") (class "Default")
      (node (ref "J1") (pin "165") (pinfunction "P$165_165") (pintype "bidirectional"))
    )
    (net (code "227") (name "unconnected-(J1-P$166-Pad166)") (class "Default")
      (node (ref "J1") (pin "166") (pinfunction "P$166_166") (pintype "bidirectional"))
    )
    (net (code "228") (name "unconnected-(J1-P$167-Pad167)") (class "Default")
      (node (ref "J1") (pin "167") (pinfunction "P$167_167") (pintype "bidirectional"))
    )
    (net (code "229") (name "unconnected-(J1-P$168-Pad168)") (class "Default")
      (node (ref "J1") (pin "168") (pinfunction "P$168_168") (pintype "bidirectional"))
    )
    (net (code "230") (name "unconnected-(J1-P$169-Pad169)") (class "Default")
      (node (ref "J1") (pin "169") (pinfunction "P$169_169") (pintype "bidirectional"))
    )
    (net (code "231") (name "unconnected-(J1-P$170-Pad170)") (class "Default")
      (node (ref "J1") (pin "170") (pinfunction "P$170_170") (pintype "bidirectional"))
    )
    (net (code "232") (name "unconnected-(J1-P$171-Pad171)") (class "Default")
      (node (ref "J1") (pin "171") (pinfunction "P$171_171") (pintype "bidirectional"))
    )
    (net (code "233") (name "unconnected-(J1-P$172-Pad172)") (class "Default")
      (node (ref "J1") (pin "172") (pinfunction "P$172_172") (pintype "bidirectional"))
    )
    (net (code "234") (name "unconnected-(J1-P$173-Pad173)") (class "Default")
      (node (ref "J1") (pin "173") (pinfunction "P$173_173") (pintype "bidirectional"))
    )
    (net (code "235") (name "unconnected-(J1-P$174-Pad174)") (class "Default")
      (node (ref "J1") (pin "174") (pinfunction "P$174_174") (pintype "bidirectional"))
    )
    (net (code "236") (name "unconnected-(J1-P$175-Pad175)") (class "Default")
      (node (ref "J1") (pin "175") (pinfunction "P$175_175") (pintype "bidirectional"))
    )
    (net (code "237") (name "unconnected-(J1-P$176-Pad176)") (class "Default")
      (node (ref "J1") (pin "176") (pinfunction "P$176_176") (pintype "bidirectional"))
    )
    (net (code "238") (name "unconnected-(J1-P$177-Pad177)") (class "Default")
      (node (ref "J1") (pin "177") (pinfunction "P$177_177") (pintype "bidirectional"))
    )
    (net (code "239") (name "unconnected-(J1-P$179-Pad179)") (class "Default")
      (node (ref "J1") (pin "179") (pinfunction "P$179_179") (pintype "bidirectional"))
    )
    (net (code "240") (name "unconnected-(U$1-SS-PadF1)") (class "Default")
      (node (ref "U$1") (pin "F1") (pinfunction "SS_F1") (pintype "bidirectional"))
    )
    (net (code "241") (name "unconnected-(U$2-SS-PadF1)") (class "Default")
      (node (ref "U$2") (pin "F1") (pinfunction "SS_F1") (pintype "bidirectional"))
    )
    (net (code "242") (name "unconnected-(U2-EP-Pad25)") (class "Default")
      (node (ref "U2") (pin "25") (pinfunction "EP_25") (pintype "power_in"))
    )
    (net (code "243") (name "unconnected-(U2-NC-Pad2)") (class "Default")
      (node (ref "U2") (pin "2") (pinfunction "NC_2") (pintype "passive"))
    )
    (net (code "244") (name "unconnected-(U2-NC_2-Pad13)") (class "Default")
      (node (ref "U2") (pin "13") (pinfunction "NC_2_13") (pintype "passive"))
    )
    (net (code "245") (name "unconnected-(U2-NC_3-Pad6)") (class "Default")
      (node (ref "U2") (pin "6") (pinfunction "NC_3_6") (pintype "passive"))
    )
    (net (code "246") (name "unconnected-(U2-NC_4-Pad12)") (class "Default")
      (node (ref "U2") (pin "12") (pinfunction "NC_4_12") (pintype "passive"))
    )
    (net (code "247") (name "unconnected-(U2-SDO-Pad16)") (class "Default")
      (node (ref "U2") (pin "16") (pinfunction "SDO_16") (pintype "passive"))
    )
    (net (code "248") (name "unconnected-(U3-NIC-Pad7)") (class "Default")
      (node (ref "U3") (pin "7") (pinfunction "NIC_7") (pintype "no_connect"))
    )
    (net (code "249") (name "unconnected-(U3-NIC_2-Pad3)") (class "Default")
      (node (ref "U3") (pin "3") (pinfunction "NIC_2_3") (pintype "no_connect"))
    )
    (net (code "250") (name "unconnected-(U3-TP-Pad8)") (class "Default")
      (node (ref "U3") (pin "8") (pinfunction "TP_8") (pintype "no_connect"))
    )
    (net (code "251") (name "unconnected-(U3-TP_2-Pad1)") (class "Default")
      (node (ref "U3") (pin "1") (pinfunction "TP_2_1") (pintype "no_connect"))
    )
    (net (code "252") (name "unconnected-(U3-TRIM-Pad5)") (class "Default")
      (node (ref "U3") (pin "5") (pinfunction "TRIM_5") (pintype "input"))
    )
    (net (code "253") (name "unconnected-(U4-~{SHDN}-Pad6)") (class "Default")
      (node (ref "U4") (pin "6") (pinfunction "~{SHDN}_6") (pintype "input"))
    )
    (net (code "254") (name "unconnected-(U6-EP-Pad25)") (class "Default")
      (node (ref "U6") (pin "25") (pinfunction "EP_25") (pintype "power_in"))
    )
    (net (code "255") (name "unconnected-(U6-NC-Pad2)") (class "Default")
      (node (ref "U6") (pin "2") (pinfunction "NC_2") (pintype "passive"))
    )
    (net (code "256") (name "unconnected-(U6-NC_2-Pad13)") (class "Default")
      (node (ref "U6") (pin "13") (pinfunction "NC_2_13") (pintype "passive"))
    )
    (net (code "257") (name "unconnected-(U6-NC_3-Pad6)") (class "Default")
      (node (ref "U6") (pin "6") (pinfunction "NC_3_6") (pintype "passive"))
    )
    (net (code "258") (name "unconnected-(U6-NC_4-Pad12)") (class "Default")
      (node (ref "U6") (pin "12") (pinfunction "NC_4_12") (pintype "passive"))
    )
    (net (code "259") (name "unconnected-(U6-SDO-Pad16)") (class "Default")
      (node (ref "U6") (pin "16") (pinfunction "SDO_16") (pintype "passive"))
    )
    (net (code "260") (name "unconnected-(U7-NIC-Pad7)") (class "Default")
      (node (ref "U7") (pin "7") (pinfunction "NIC_7") (pintype "no_connect"))
    )
    (net (code "261") (name "unconnected-(U7-NIC_2-Pad3)") (class "Default")
      (node (ref "U7") (pin "3") (pinfunction "NIC_2_3") (pintype "no_connect"))
    )
    (net (code "262") (name "unconnected-(U7-TP-Pad8)") (class "Default")
      (node (ref "U7") (pin "8") (pinfunction "TP_8") (pintype "no_connect"))
    )
    (net (code "263") (name "unconnected-(U7-TP_2-Pad1)") (class "Default")
      (node (ref "U7") (pin "1") (pinfunction "TP_2_1") (pintype "no_connect"))
    )
    (net (code "264") (name "unconnected-(U7-TRIM-Pad5)") (class "Default")
      (node (ref "U7") (pin "5") (pinfunction "TRIM_5") (pintype "input"))
    )
  )
)
